# gator.net
KiCad netlist of a schematic drawn in EAGLE
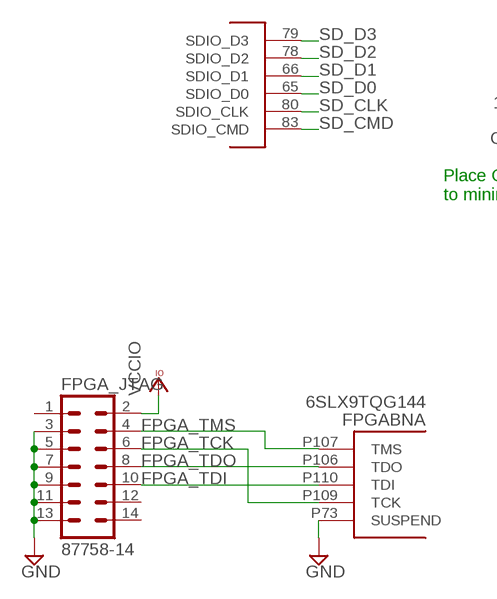
[diagram p0: schematic, sheet 1, part 1 of 2]
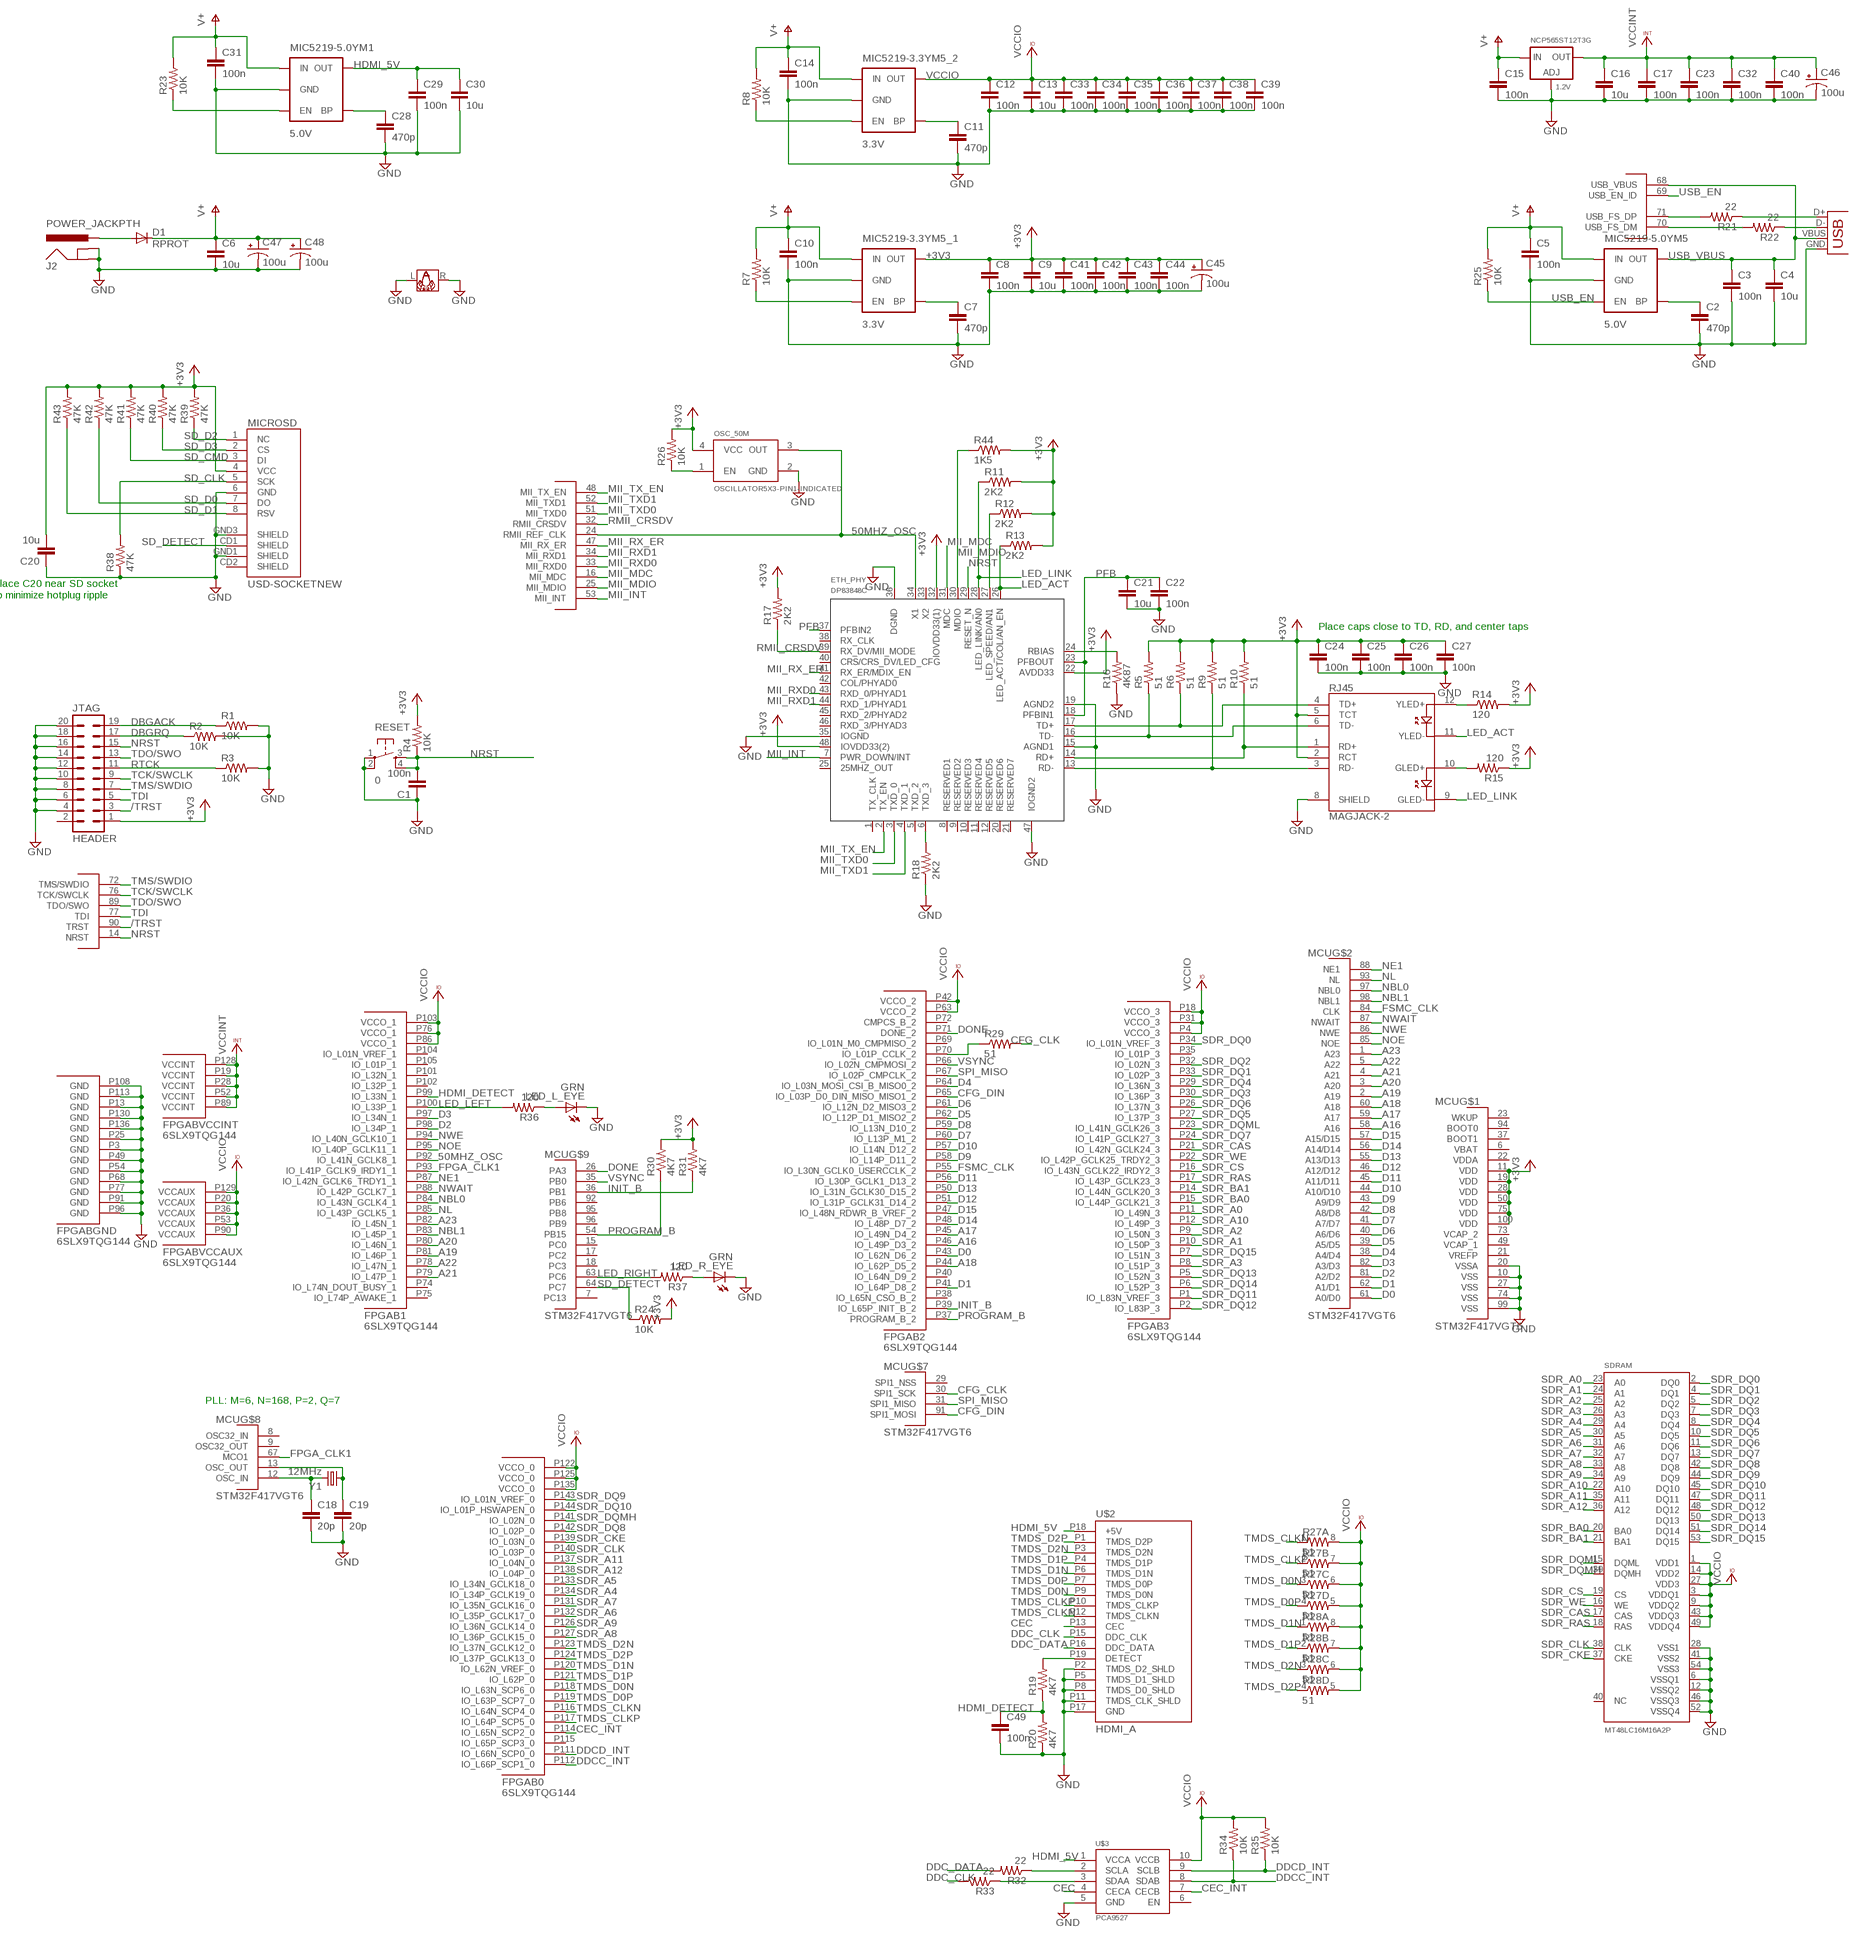
[diagram p1: schematic, sheet 1, part 2 of 2]

(export (version "E")
  (design (tool "Eeschema 10.0.6"))
  (components
    (comp (ref "C1")
      (value "100n")
      (footprint "eagle-import:0603-CAP")
      (libsource (lib "eagle-import") (part "CAP0603-CAP"))
    )
    (comp (ref "C2")
      (value "470p")
      (footprint "eagle-import:0603-CAP")
      (libsource (lib "eagle-import") (part "CAP0603-CAP"))
    )
    (comp (ref "C3")
      (value "100n")
      (footprint "eagle-import:0603-CAP")
      (libsource (lib "eagle-import") (part "CAP0603-CAP"))
    )
    (comp (ref "C4")
      (value "10u")
      (footprint "eagle-import:0603-CAP")
      (libsource (lib "eagle-import") (part "CAP0603-CAP"))
    )
    (comp (ref "C5")
      (value "100n")
      (footprint "eagle-import:0603-CAP")
      (libsource (lib "eagle-import") (part "CAP0603-CAP"))
    )
    (comp (ref "C6")
      (value "10u")
      (footprint "eagle-import:0603-CAP")
      (libsource (lib "eagle-import") (part "CAP0603-CAP"))
    )
    (comp (ref "C7")
      (value "470p")
      (footprint "eagle-import:0603-CAP")
      (libsource (lib "eagle-import") (part "CAP0603-CAP"))
    )
    (comp (ref "C8")
      (value "100n")
      (footprint "eagle-import:0603-CAP")
      (libsource (lib "eagle-import") (part "CAP0603-CAP"))
    )
    (comp (ref "C9")
      (value "10u")
      (footprint "eagle-import:0603-CAP")
      (libsource (lib "eagle-import") (part "CAP0603-CAP"))
    )
    (comp (ref "C10")
      (value "100n")
      (footprint "eagle-import:0603-CAP")
      (libsource (lib "eagle-import") (part "CAP0603-CAP"))
    )
    (comp (ref "C11")
      (value "470p")
      (footprint "eagle-import:0603-CAP")
      (libsource (lib "eagle-import") (part "CAP0603-CAP"))
    )
    (comp (ref "C12")
      (value "100n")
      (footprint "eagle-import:0603-CAP")
      (libsource (lib "eagle-import") (part "CAP0603-CAP"))
    )
    (comp (ref "C13")
      (value "10u")
      (footprint "eagle-import:0603-CAP")
      (libsource (lib "eagle-import") (part "CAP0603-CAP"))
    )
    (comp (ref "C14")
      (value "100n")
      (footprint "eagle-import:0603-CAP")
      (libsource (lib "eagle-import") (part "CAP0603-CAP"))
    )
    (comp (ref "C15")
      (value "100n")
      (footprint "eagle-import:0603-CAP")
      (libsource (lib "eagle-import") (part "CAP0603-CAP"))
    )
    (comp (ref "C16")
      (value "10u")
      (footprint "eagle-import:0603-CAP")
      (libsource (lib "eagle-import") (part "CAP0603-CAP"))
    )
    (comp (ref "C17")
      (value "100n")
      (footprint "eagle-import:0603-CAP")
      (libsource (lib "eagle-import") (part "CAP0603-CAP"))
    )
    (comp (ref "C18")
      (value "20p")
      (footprint "eagle-import:0603-CAP")
      (libsource (lib "eagle-import") (part "CAP0603-CAP"))
    )
    (comp (ref "C19")
      (value "20p")
      (footprint "eagle-import:0603-CAP")
      (libsource (lib "eagle-import") (part "CAP0603-CAP"))
    )
    (comp (ref "C20")
      (value "10u")
      (footprint "eagle-import:0603-CAP")
      (libsource (lib "eagle-import") (part "CAP0603-CAP"))
    )
    (comp (ref "C21")
      (value "10u")
      (footprint "eagle-import:0603-CAP")
      (libsource (lib "eagle-import") (part "CAP0603-CAP"))
    )
    (comp (ref "C22")
      (value "100n")
      (footprint "eagle-import:0603-CAP")
      (libsource (lib "eagle-import") (part "CAP0603-CAP"))
    )
    (comp (ref "C23")
      (value "100n")
      (footprint "eagle-import:0603-CAP")
      (libsource (lib "eagle-import") (part "CAP0603-CAP"))
    )
    (comp (ref "C24")
      (value "100n")
      (footprint "eagle-import:0603-CAP")
      (libsource (lib "eagle-import") (part "CAP0603-CAP"))
    )
    (comp (ref "C25")
      (value "100n")
      (footprint "eagle-import:0603-CAP")
      (libsource (lib "eagle-import") (part "CAP0603-CAP"))
    )
    (comp (ref "C26")
      (value "100n")
      (footprint "eagle-import:0603-CAP")
      (libsource (lib "eagle-import") (part "CAP0603-CAP"))
    )
    (comp (ref "C27")
      (value "100n")
      (footprint "eagle-import:0603-CAP")
      (libsource (lib "eagle-import") (part "CAP0603-CAP"))
    )
    (comp (ref "C28")
      (value "470p")
      (footprint "eagle-import:0603-CAP")
      (libsource (lib "eagle-import") (part "CAP0603-CAP"))
    )
    (comp (ref "C29")
      (value "100n")
      (footprint "eagle-import:0603-CAP")
      (libsource (lib "eagle-import") (part "CAP0603-CAP"))
    )
    (comp (ref "C30")
      (value "10u")
      (footprint "eagle-import:0603-CAP")
      (libsource (lib "eagle-import") (part "CAP0603-CAP"))
    )
    (comp (ref "C31")
      (value "100n")
      (footprint "eagle-import:0603-CAP")
      (libsource (lib "eagle-import") (part "CAP0603-CAP"))
    )
    (comp (ref "C32")
      (value "100n")
      (footprint "eagle-import:0603-CAP")
      (libsource (lib "eagle-import") (part "CAP0603-CAP"))
    )
    (comp (ref "C33")
      (value "100n")
      (footprint "eagle-import:0603-CAP")
      (libsource (lib "eagle-import") (part "CAP0603-CAP"))
    )
    (comp (ref "C34")
      (value "100n")
      (footprint "eagle-import:0603-CAP")
      (libsource (lib "eagle-import") (part "CAP0603-CAP"))
    )
    (comp (ref "C35")
      (value "100n")
      (footprint "eagle-import:0603-CAP")
      (libsource (lib "eagle-import") (part "CAP0603-CAP"))
    )
    (comp (ref "C36")
      (value "100n")
      (footprint "eagle-import:0603-CAP")
      (libsource (lib "eagle-import") (part "CAP0603-CAP"))
    )
    (comp (ref "C37")
      (value "100n")
      (footprint "eagle-import:0603-CAP")
      (libsource (lib "eagle-import") (part "CAP0603-CAP"))
    )
    (comp (ref "C38")
      (value "100n")
      (footprint "eagle-import:0603-CAP")
      (libsource (lib "eagle-import") (part "CAP0603-CAP"))
    )
    (comp (ref "C39")
      (value "100n")
      (footprint "eagle-import:0603-CAP")
      (libsource (lib "eagle-import") (part "CAP0603-CAP"))
    )
    (comp (ref "C40")
      (value "100n")
      (footprint "eagle-import:0603-CAP")
      (libsource (lib "eagle-import") (part "CAP0603-CAP"))
    )
    (comp (ref "C41")
      (value "100n")
      (footprint "eagle-import:0603-CAP")
      (libsource (lib "eagle-import") (part "CAP0603-CAP"))
    )
    (comp (ref "C42")
      (value "100n")
      (footprint "eagle-import:0603-CAP")
      (libsource (lib "eagle-import") (part "CAP0603-CAP"))
    )
    (comp (ref "C43")
      (value "100n")
      (footprint "eagle-import:0603-CAP")
      (libsource (lib "eagle-import") (part "CAP0603-CAP"))
    )
    (comp (ref "C44")
      (value "100n")
      (footprint "eagle-import:0603-CAP")
      (libsource (lib "eagle-import") (part "CAP0603-CAP"))
    )
    (comp (ref "C45")
      (value "100u")
      (footprint "eagle-import:CPOL-RADIAL-100UF-25V")
      (libsource (lib "eagle-import") (part "CAP_POLPTH1"))
    )
    (comp (ref "C46")
      (value "100u")
      (footprint "eagle-import:CPOL-RADIAL-100UF-25V")
      (libsource (lib "eagle-import") (part "CAP_POLPTH1"))
    )
    (comp (ref "C47")
      (value "100u")
      (footprint "eagle-import:CPOL-RADIAL-100UF-25V")
      (libsource (lib "eagle-import") (part "CAP_POLPTH1"))
    )
    (comp (ref "C48")
      (value "100u")
      (footprint "eagle-import:CPOL-RADIAL-100UF-25V")
      (libsource (lib "eagle-import") (part "CAP_POLPTH1"))
    )
    (comp (ref "C49")
      (value "100n")
      (footprint "eagle-import:0603-CAP")
      (libsource (lib "eagle-import") (part "CAP0603-CAP"))
    )
    (comp (ref "D1")
      (value "RPROT")
      (footprint "eagle-import:DIODE-1N4001")
      (fields (field (name "MANF") "STMicroelectronics"))
      (libsource (lib "eagle-import") (part "DIODEPTH"))
    )
    (comp (ref "ETH_PHY")
      (value "DP83848C")
      (footprint "eagle-import:LQFP-48")
      (fields (field (name "MANF") "Texas Instruments"))
      (libsource (lib "eagle-import") (part "DP83848C"))
    )
    (comp (ref "FPGA")
      (value "6SLX9TQG144")
      (footprint "eagle-import:TQ144")
      (fields
        (field (name "DIGIKEY#") "122-1745-ND")
        (field (name "MANF") "Xilinx Inc")
        (field (name "MANF#") "XC6SLX9-2TQG144C")
      )
      (libsource (lib "eagle-import") (part "6SLX9TQG144"))
    )
    (comp (ref "FPGA_JTAG")
      (value "87758-14")
      (footprint "eagle-import:87758-14")
      (fields (field (name "MANF") "Assmann WSW Components"))
      (libsource (lib "eagle-import") (part "87758-14"))
    )
    (comp (ref "J2")
      (value "POWER_JACKPTH")
      (footprint "eagle-import:POWER_JACK_PTH")
      (fields (field (name "MANF") "CUI Inc"))
      (libsource (lib "eagle-import") (part "POWER_JACKPTH"))
    )
    (comp (ref "JTAG")
      (value "HEADER")
      (footprint "eagle-import:ML20")
      (fields (field (name "MANF") "Sullins Connector Solutions"))
      (libsource (lib "eagle-import") (part "ML20"))
    )
    (comp (ref "LED_L_EYE")
      (value "GRN")
      (footprint "eagle-import:LED3MM")
      (fields (field (name "MANF") "Lite-On Inc"))
      (libsource (lib "eagle-import") (part "LED3MM"))
    )
    (comp (ref "LED_R_EYE")
      (value "GRN")
      (footprint "eagle-import:LED3MM")
      (fields (field (name "MANF") "Lite-On Inc"))
      (libsource (lib "eagle-import") (part "LED3MM"))
    )
    (comp (ref "MCU")
      (value "STM32F417VGT6")
      (footprint "eagle-import:LQFP-100")
      (fields
        (field (name "DIGIKEY#") "497-11900-ND")
        (field (name "MANF") "STMicroelectronics")
        (field (name "MANF#") "STM32F417VGT6")
      )
      (libsource (lib "eagle-import") (part "STM32F417VGT6"))
    )
    (comp (ref "MIC5219-3.3YM5_1")
      (value "3.3V")
      (footprint "eagle-import:SOT23-5")
      (fields (field (name "MANF") "Micrel Inc"))
      (libsource (lib "eagle-import") (part "V_REG_LDOSMD"))
    )
    (comp (ref "MIC5219-3.3YM5_2")
      (value "3.3V")
      (footprint "eagle-import:SOT23-5")
      (fields (field (name "MANF") "Micrel Inc"))
      (libsource (lib "eagle-import") (part "V_REG_LDOSMD"))
    )
    (comp (ref "MIC5219-5.0YM1")
      (value "5.0V")
      (footprint "eagle-import:SOT23-5")
      (fields (field (name "MANF") "Micrel Inc"))
      (libsource (lib "eagle-import") (part "V_REG_LDOSMD"))
    )
    (comp (ref "MIC5219-5.0YM5")
      (value "5.0V")
      (footprint "eagle-import:SOT23-5")
      (fields (field (name "MANF") "Micrel Inc"))
      (libsource (lib "eagle-import") (part "V_REG_LDOSMD"))
    )
    (comp (ref "MICROSD")
      (value "USD-SOCKETNEW")
      (footprint "eagle-import:MICRO-SD-SOCKET-PP")
      (fields (field (name "MANF") "Amphenol Commercial Products"))
      (libsource (lib "eagle-import") (part "USD-SOCKETNEW"))
    )
    (comp (ref "NCP565ST12T3G")
      (value "1.2V")
      (footprint "eagle-import:SOT223-R")
      (fields (field (name "MANF") "ON Semiconductor"))
      (libsource (lib "eagle-import") (part "LM1117SOT223-REFLOW"))
    )
    (comp (ref "OSC_50M")
      (value "OSCILLATOR5X3-PIN1-INDICATED")
      (footprint "eagle-import:CRYSTAL-OSC-SMD-5X3")
      (fields (field (name "MANF") "CTS-Frequency Controls"))
      (libsource (lib "eagle-import") (part "OSCILLATOR5X3-PIN1-INDICATED"))
    )
    (comp (ref "R1")
      (value "10K")
      (footprint "eagle-import:0603-RES")
      (libsource (lib "eagle-import") (part "RESISTOR0603-RES"))
    )
    (comp (ref "R2")
      (value "10K")
      (footprint "eagle-import:0603-RES")
      (libsource (lib "eagle-import") (part "RESISTOR0603-RES"))
    )
    (comp (ref "R3")
      (value "10K")
      (footprint "eagle-import:0603-RES")
      (libsource (lib "eagle-import") (part "RESISTOR0603-RES"))
    )
    (comp (ref "R4")
      (value "10K")
      (footprint "eagle-import:0603-RES")
      (libsource (lib "eagle-import") (part "RESISTOR0603-RES"))
    )
    (comp (ref "R5")
      (value "51")
      (footprint "eagle-import:0603-RES")
      (libsource (lib "eagle-import") (part "RESISTOR0603-RES"))
    )
    (comp (ref "R6")
      (value "51")
      (footprint "eagle-import:0603-RES")
      (libsource (lib "eagle-import") (part "RESISTOR0603-RES"))
    )
    (comp (ref "R7")
      (value "10K")
      (footprint "eagle-import:0603-RES")
      (libsource (lib "eagle-import") (part "RESISTOR0603-RES"))
    )
    (comp (ref "R8")
      (value "10K")
      (footprint "eagle-import:0603-RES")
      (libsource (lib "eagle-import") (part "RESISTOR0603-RES"))
    )
    (comp (ref "R9")
      (value "51")
      (footprint "eagle-import:0603-RES")
      (libsource (lib "eagle-import") (part "RESISTOR0603-RES"))
    )
    (comp (ref "R10")
      (value "51")
      (footprint "eagle-import:0603-RES")
      (libsource (lib "eagle-import") (part "RESISTOR0603-RES"))
    )
    (comp (ref "R11")
      (value "2K2")
      (footprint "eagle-import:0603-RES")
      (libsource (lib "eagle-import") (part "RESISTOR0603-RES"))
    )
    (comp (ref "R12")
      (value "2K2")
      (footprint "eagle-import:0603-RES")
      (libsource (lib "eagle-import") (part "RESISTOR0603-RES"))
    )
    (comp (ref "R13")
      (value "2K2")
      (footprint "eagle-import:0603-RES")
      (libsource (lib "eagle-import") (part "RESISTOR0603-RES"))
    )
    (comp (ref "R14")
      (value "120")
      (footprint "eagle-import:0603-RES")
      (libsource (lib "eagle-import") (part "RESISTOR0603-RES"))
    )
    (comp (ref "R15")
      (value "120")
      (footprint "eagle-import:0603-RES")
      (libsource (lib "eagle-import") (part "RESISTOR0603-RES"))
    )
    (comp (ref "R16")
      (value "4K87")
      (footprint "eagle-import:0603-RES")
      (libsource (lib "eagle-import") (part "RESISTOR0603-RES"))
    )
    (comp (ref "R17")
      (value "2K2")
      (footprint "eagle-import:0603-RES")
      (libsource (lib "eagle-import") (part "RESISTOR0603-RES"))
    )
    (comp (ref "R18")
      (value "2K2")
      (footprint "eagle-import:0603-RES")
      (libsource (lib "eagle-import") (part "RESISTOR0603-RES"))
    )
    (comp (ref "R19")
      (value "4K7")
      (footprint "eagle-import:0603-RES")
      (libsource (lib "eagle-import") (part "RESISTOR0603-RES"))
    )
    (comp (ref "R20")
      (value "4K7")
      (footprint "eagle-import:0603-RES")
      (libsource (lib "eagle-import") (part "RESISTOR0603-RES"))
    )
    (comp (ref "R21")
      (value "22")
      (footprint "eagle-import:0603-RES")
      (libsource (lib "eagle-import") (part "RESISTOR0603-RES"))
    )
    (comp (ref "R22")
      (value "22")
      (footprint "eagle-import:0603-RES")
      (libsource (lib "eagle-import") (part "RESISTOR0603-RES"))
    )
    (comp (ref "R23")
      (value "10K")
      (footprint "eagle-import:0603-RES")
      (libsource (lib "eagle-import") (part "RESISTOR0603-RES"))
    )
    (comp (ref "R24")
      (value "10K")
      (footprint "eagle-import:0603-RES")
      (libsource (lib "eagle-import") (part "RESISTOR0603-RES"))
    )
    (comp (ref "R25")
      (value "10K")
      (footprint "eagle-import:0603-RES")
      (libsource (lib "eagle-import") (part "RESISTOR0603-RES"))
    )
    (comp (ref "R26")
      (value "10K")
      (footprint "eagle-import:0603-RES")
      (libsource (lib "eagle-import") (part "RESISTOR0603-RES"))
    )
    (comp (ref "R27")
      (value "51")
      (footprint "eagle-import:0603-ARV")
      (fields
        (field (name "MANF") "Yageo")
        (field (name "DIGIKEY#") "YC164J-51CT-ND")
        (field (name "MANF#") "YC164-JR-0751RL")
      )
      (libsource (lib "eagle-import") (part "RESISTOR-ARRAY0603-ARV"))
    )
    (comp (ref "R28")
      (value "51")
      (footprint "eagle-import:0603-ARV")
      (fields
        (field (name "MANF") "Yageo")
        (field (name "DIGIKEY#") "YC164J-51CT-ND")
        (field (name "MANF#") "YC164-JR-0751RL")
      )
      (libsource (lib "eagle-import") (part "RESISTOR-ARRAY0603-ARV"))
    )
    (comp (ref "R29")
      (value "51")
      (footprint "eagle-import:0603-RES")
      (libsource (lib "eagle-import") (part "RESISTOR0603-RES"))
    )
    (comp (ref "R30")
      (value "4K7")
      (footprint "eagle-import:0603-RES")
      (libsource (lib "eagle-import") (part "RESISTOR0603-RES"))
    )
    (comp (ref "R31")
      (value "4K7")
      (footprint "eagle-import:0603-RES")
      (libsource (lib "eagle-import") (part "RESISTOR0603-RES"))
    )
    (comp (ref "R32")
      (value "22")
      (footprint "eagle-import:0603-RES")
      (libsource (lib "eagle-import") (part "RESISTOR0603-RES"))
    )
    (comp (ref "R33")
      (value "22")
      (footprint "eagle-import:0603-RES")
      (libsource (lib "eagle-import") (part "RESISTOR0603-RES"))
    )
    (comp (ref "R34")
      (value "10K")
      (footprint "eagle-import:0603-RES")
      (libsource (lib "eagle-import") (part "RESISTOR0603-RES"))
    )
    (comp (ref "R35")
      (value "10K")
      (footprint "eagle-import:0603-RES")
      (libsource (lib "eagle-import") (part "RESISTOR0603-RES"))
    )
    (comp (ref "R36")
      (value "120")
      (footprint "eagle-import:0603-RES")
      (libsource (lib "eagle-import") (part "RESISTOR0603-RES"))
    )
    (comp (ref "R37")
      (value "120")
      (footprint "eagle-import:0603-RES")
      (libsource (lib "eagle-import") (part "RESISTOR0603-RES"))
    )
    (comp (ref "R38")
      (value "47K")
      (footprint "eagle-import:0603-RES")
      (libsource (lib "eagle-import") (part "RESISTOR0603-RES"))
    )
    (comp (ref "R39")
      (value "47K")
      (footprint "eagle-import:0603-RES")
      (libsource (lib "eagle-import") (part "RESISTOR0603-RES"))
    )
    (comp (ref "R40")
      (value "47K")
      (footprint "eagle-import:0603-RES")
      (libsource (lib "eagle-import") (part "RESISTOR0603-RES"))
    )
    (comp (ref "R41")
      (value "47K")
      (footprint "eagle-import:0603-RES")
      (libsource (lib "eagle-import") (part "RESISTOR0603-RES"))
    )
    (comp (ref "R42")
      (value "47K")
      (footprint "eagle-import:0603-RES")
      (libsource (lib "eagle-import") (part "RESISTOR0603-RES"))
    )
    (comp (ref "R43")
      (value "47K")
      (footprint "eagle-import:0603-RES")
      (libsource (lib "eagle-import") (part "RESISTOR0603-RES"))
    )
    (comp (ref "R44")
      (value "1K5")
      (footprint "eagle-import:0603-RES")
      (libsource (lib "eagle-import") (part "RESISTOR0603-RES"))
    )
    (comp (ref "RESET")
      (value "0")
      (footprint "eagle-import:TACTILE-PTH")
      (libsource (lib "eagle-import") (part "TAC_SWITCHPTH"))
    )
    (comp (ref "RJ45")
      (value "MAGJACK-2")
      (footprint "eagle-import:MAGJACK-19938")
      (fields (field (name "MANF") "Stewart Connector"))
      (libsource (lib "eagle-import") (part "MAGJACK-2"))
    )
    (comp (ref "SDRAM")
      (value "MT48LC16M16A2P")
      (footprint "eagle-import:TSOP54-400")
      (fields (field (name "MANF") "Micron Technology Inc"))
      (libsource (lib "eagle-import") (part "MT48LC16M16A2P"))
    )
    (comp (ref "U$2")
      (value "HDMI_A")
      (footprint "eagle-import:HDMI_A_SMT")
      (fields (field (name "MANF") "Molex Inc"))
      (libsource (lib "eagle-import") (part "HDMI_A"))
    )
    (comp (ref "U$3")
      (value "PCA9527")
      (footprint "eagle-import:TSSOP10")
      (fields (field (name "MANF") "NXP Semiconductors"))
      (libsource (lib "eagle-import") (part "PCA9527"))
    )
    (comp (ref "U$4")
      (value "GATOR_HEAD")
      (footprint "eagle-import:GATOR_HEAD")
      (fields (field (name "MANF") "CUI Inc"))
      (libsource (lib "eagle-import") (part "GATOR_HEAD"))
    )
    (comp (ref "X1")
      (value "USB-A-S")
      (footprint "eagle-import:USB-A-S")
      (fields (field (name "MANF") "CNC Tech"))
      (libsource (lib "eagle-import") (part "USB-A-S"))
    )
    (comp (ref "Y1")
      (value "12MHz")
      (footprint "eagle-import:HC49US")
      (fields (field (name "MANF") "CTS-Frequency Controls"))
      (libsource (lib "eagle-import") (part "CRYSTALHC49US"))
    )
  )
  (nets
    (net (code "1") (name "+3V3") (class "Default")
      (node (ref "C20") (pin "2") (pinfunction "2_2") (pintype "passive"))
      (node (ref "C24") (pin "1") (pinfunction "1_1") (pintype "passive"))
      (node (ref "C25") (pin "1") (pinfunction "1_1") (pintype "passive"))
      (node (ref "C26") (pin "1") (pinfunction "1_1") (pintype "passive"))
      (node (ref "C27") (pin "1") (pinfunction "1_1") (pintype "passive"))
      (node (ref "C41") (pin "1") (pinfunction "1_1") (pintype "passive"))
      (node (ref "C42") (pin "1") (pinfunction "1_1") (pintype "passive"))
      (node (ref "C43") (pin "1") (pinfunction "1_1") (pintype "passive"))
      (node (ref "C44") (pin "1") (pinfunction "1_1") (pintype "passive"))
      (node (ref "C45") (pin "1") (pinfunction "+_1") (pintype "passive"))
      (node (ref "C8") (pin "1") (pinfunction "1_1") (pintype "passive"))
      (node (ref "C9") (pin "1") (pinfunction "1_1") (pintype "passive"))
      (node (ref "ETH_PHY") (pin "22") (pinfunction "AVDD33_22") (pintype "bidirectional"))
      (node (ref "ETH_PHY") (pin "32") (pinfunction "IOVDD33(1)_32") (pintype "bidirectional"))
      (node (ref "ETH_PHY") (pin "48") (pinfunction "IOVDD33(2)_48") (pintype "bidirectional"))
      (node (ref "JTAG") (pin "1") (pinfunction "1_1") (pintype "passive"))
      (node (ref "MCU") (pin "100") (pinfunction "VDD_100") (pintype "bidirectional"))
      (node (ref "MCU") (pin "11") (pinfunction "VDD_11") (pintype "bidirectional"))
      (node (ref "MCU") (pin "19") (pinfunction "VDD_19") (pintype "bidirectional"))
      (node (ref "MCU") (pin "28") (pinfunction "VDD_28") (pintype "bidirectional"))
      (node (ref "MCU") (pin "50") (pinfunction "VDD_50") (pintype "bidirectional"))
      (node (ref "MCU") (pin "75") (pinfunction "VDD_75") (pintype "bidirectional"))
      (node (ref "MIC5219-3.3YM5_1") (pin "5") (pinfunction "OUT_5") (pintype "passive"))
      (node (ref "MICROSD") (pin "4") (pinfunction "VCC_4") (pintype "bidirectional"))
      (node (ref "OSC_50M") (pin "4") (pinfunction "VCC_4") (pintype "bidirectional"))
      (node (ref "R10") (pin "2") (pinfunction "2_2") (pintype "passive"))
      (node (ref "R11") (pin "2") (pinfunction "2_2") (pintype "passive"))
      (node (ref "R12") (pin "2") (pinfunction "2_2") (pintype "passive"))
      (node (ref "R13") (pin "2") (pinfunction "2_2") (pintype "passive"))
      (node (ref "R14") (pin "2") (pinfunction "2_2") (pintype "passive"))
      (node (ref "R15") (pin "1") (pinfunction "1_1") (pintype "passive"))
      (node (ref "R17") (pin "2") (pinfunction "2_2") (pintype "passive"))
      (node (ref "R24") (pin "2") (pinfunction "2_2") (pintype "passive"))
      (node (ref "R26") (pin "2") (pinfunction "2_2") (pintype "passive"))
      (node (ref "R30") (pin "2") (pinfunction "2_2") (pintype "passive"))
      (node (ref "R31") (pin "2") (pinfunction "2_2") (pintype "passive"))
      (node (ref "R39") (pin "2") (pinfunction "2_2") (pintype "passive"))
      (node (ref "R4") (pin "2") (pinfunction "2_2") (pintype "passive"))
      (node (ref "R40") (pin "2") (pinfunction "2_2") (pintype "passive"))
      (node (ref "R41") (pin "2") (pinfunction "2_2") (pintype "passive"))
      (node (ref "R42") (pin "2") (pinfunction "2_2") (pintype "passive"))
      (node (ref "R43") (pin "2") (pinfunction "2_2") (pintype "passive"))
      (node (ref "R44") (pin "2") (pinfunction "2_2") (pintype "passive"))
      (node (ref "R5") (pin "2") (pinfunction "2_2") (pintype "passive"))
      (node (ref "R6") (pin "2") (pinfunction "2_2") (pintype "passive"))
      (node (ref "R9") (pin "2") (pinfunction "2_2") (pintype "passive"))
      (node (ref "RJ45") (pin "2") (pinfunction "RCT_2") (pintype "bidirectional"))
      (node (ref "RJ45") (pin "5") (pinfunction "TCT_5") (pintype "bidirectional"))
    )
    (net (code "2") (name "/50MHZ_OSC") (class "Default")
      (node (ref "ETH_PHY") (pin "34") (pinfunction "X1_34") (pintype "bidirectional"))
      (node (ref "FPGA") (pin "P92") (pinfunction "IO_L41N_GCLK8_1_P92") (pintype "bidirectional"))
      (node (ref "MCU") (pin "24") (pinfunction "RMII_REF_CLK_24") (pintype "bidirectional"))
      (node (ref "OSC_50M") (pin "3") (pinfunction "OUT_3") (pintype "bidirectional"))
    )
    (net (code "3") (name "/A16") (class "Default")
      (node (ref "FPGA") (pin "P46") (pinfunction "IO_L49P_D3_2_P46") (pintype "bidirectional"))
      (node (ref "MCU") (pin "58") (pinfunction "A16_58") (pintype "bidirectional"))
    )
    (net (code "4") (name "/A17") (class "Default")
      (node (ref "FPGA") (pin "P45") (pinfunction "IO_L49N_D4_2_P45") (pintype "bidirectional"))
      (node (ref "MCU") (pin "59") (pinfunction "A17_59") (pintype "bidirectional"))
    )
    (net (code "5") (name "/A18") (class "Default")
      (node (ref "FPGA") (pin "P44") (pinfunction "IO_L62P_D5_2_P44") (pintype "bidirectional"))
      (node (ref "MCU") (pin "60") (pinfunction "A18_60") (pintype "bidirectional"))
    )
    (net (code "6") (name "/A19") (class "Default")
      (node (ref "FPGA") (pin "P81") (pinfunction "IO_L46P_1_P81") (pintype "bidirectional"))
      (node (ref "MCU") (pin "2") (pinfunction "A19_2") (pintype "bidirectional"))
    )
    (net (code "7") (name "/A20") (class "Default")
      (node (ref "FPGA") (pin "P80") (pinfunction "IO_L46N_1_P80") (pintype "bidirectional"))
      (node (ref "MCU") (pin "3") (pinfunction "A20_3") (pintype "bidirectional"))
    )
    (net (code "8") (name "/A21") (class "Default")
      (node (ref "FPGA") (pin "P79") (pinfunction "IO_L47P_1_P79") (pintype "bidirectional"))
      (node (ref "MCU") (pin "4") (pinfunction "A21_4") (pintype "bidirectional"))
    )
    (net (code "9") (name "/A22") (class "Default")
      (node (ref "FPGA") (pin "P78") (pinfunction "IO_L47N_1_P78") (pintype "bidirectional"))
      (node (ref "MCU") (pin "5") (pinfunction "A22_5") (pintype "bidirectional"))
    )
    (net (code "10") (name "/A23") (class "Default")
      (node (ref "FPGA") (pin "P82") (pinfunction "IO_L45N_1_P82") (pintype "bidirectional"))
      (node (ref "MCU") (pin "1") (pinfunction "A23_1") (pintype "bidirectional"))
    )
    (net (code "11") (name "/CEC") (class "Default")
      (node (ref "U$2") (pin "P13") (pinfunction "CEC_P13") (pintype "bidirectional"))
      (node (ref "U$3") (pin "4") (pinfunction "CECA_4") (pintype "bidirectional"))
    )
    (net (code "12") (name "/CEC_INT") (class "Default")
      (node (ref "FPGA") (pin "P114") (pinfunction "IO_L65N_SCP2_0_P114") (pintype "bidirectional"))
      (node (ref "U$3") (pin "7") (pinfunction "CECB_7") (pintype "bidirectional"))
    )
    (net (code "13") (name "/CFG_CLK") (class "Default")
      (node (ref "MCU") (pin "30") (pinfunction "SPI1_SCK_30") (pintype "bidirectional"))
      (node (ref "R29") (pin "2") (pinfunction "2_2") (pintype "passive"))
    )
    (net (code "14") (name "/CFG_DIN") (class "Default")
      (node (ref "FPGA") (pin "P65") (pinfunction "IO_L03P_D0_DIN_MISO_MISO1_2_P65") (pintype "bidirectional"))
      (node (ref "MCU") (pin "91") (pinfunction "SPI1_MOSI_91") (pintype "bidirectional"))
    )
    (net (code "15") (name "/D0") (class "Default")
      (node (ref "FPGA") (pin "P43") (pinfunction "IO_L62N_D6_2_P43") (pintype "bidirectional"))
      (node (ref "MCU") (pin "61") (pinfunction "A0/D0_61") (pintype "bidirectional"))
    )
    (net (code "16") (name "/D1") (class "Default")
      (node (ref "FPGA") (pin "P41") (pinfunction "IO_L64P_D8_2_P41") (pintype "bidirectional"))
      (node (ref "MCU") (pin "62") (pinfunction "A1/D1_62") (pintype "bidirectional"))
    )
    (net (code "17") (name "/D2") (class "Default")
      (node (ref "FPGA") (pin "P98") (pinfunction "IO_L34P_1_P98") (pintype "bidirectional"))
      (node (ref "MCU") (pin "81") (pinfunction "A2/D2_81") (pintype "bidirectional"))
    )
    (net (code "18") (name "/D3") (class "Default")
      (node (ref "FPGA") (pin "P97") (pinfunction "IO_L34N_1_P97") (pintype "bidirectional"))
      (node (ref "MCU") (pin "82") (pinfunction "A3/D3_82") (pintype "bidirectional"))
    )
    (net (code "19") (name "/D4") (class "Default")
      (node (ref "FPGA") (pin "P64") (pinfunction "IO_L03N_MOSI_CSI_B_MISO0_2_P64") (pintype "bidirectional"))
      (node (ref "MCU") (pin "38") (pinfunction "A4/D4_38") (pintype "bidirectional"))
    )
    (net (code "20") (name "/D5") (class "Default")
      (node (ref "FPGA") (pin "P62") (pinfunction "IO_L12P_D1_MISO2_2_P62") (pintype "bidirectional"))
      (node (ref "MCU") (pin "39") (pinfunction "A5/D5_39") (pintype "bidirectional"))
    )
    (net (code "21") (name "/D6") (class "Default")
      (node (ref "FPGA") (pin "P61") (pinfunction "IO_L12N_D2_MISO3_2_P61") (pintype "bidirectional"))
      (node (ref "MCU") (pin "40") (pinfunction "A6/D6_40") (pintype "bidirectional"))
    )
    (net (code "22") (name "/D7") (class "Default")
      (node (ref "FPGA") (pin "P60") (pinfunction "IO_L13P_M1_2_P60") (pintype "bidirectional"))
      (node (ref "MCU") (pin "41") (pinfunction "A7/D7_41") (pintype "bidirectional"))
    )
    (net (code "23") (name "/D8") (class "Default")
      (node (ref "FPGA") (pin "P59") (pinfunction "IO_L13N_D10_2_P59") (pintype "bidirectional"))
      (node (ref "MCU") (pin "42") (pinfunction "A8/D8_42") (pintype "bidirectional"))
    )
    (net (code "24") (name "/D9") (class "Default")
      (node (ref "FPGA") (pin "P58") (pinfunction "IO_L14P_D11_2_P58") (pintype "bidirectional"))
      (node (ref "MCU") (pin "43") (pinfunction "A9/D9_43") (pintype "bidirectional"))
    )
    (net (code "25") (name "/D10") (class "Default")
      (node (ref "FPGA") (pin "P57") (pinfunction "IO_L14N_D12_2_P57") (pintype "bidirectional"))
      (node (ref "MCU") (pin "44") (pinfunction "A10/D10_44") (pintype "bidirectional"))
    )
    (net (code "26") (name "/D11") (class "Default")
      (node (ref "FPGA") (pin "P56") (pinfunction "IO_L30P_GCLK1_D13_2_P56") (pintype "bidirectional"))
      (node (ref "MCU") (pin "45") (pinfunction "A11/D11_45") (pintype "bidirectional"))
    )
    (net (code "27") (name "/D12") (class "Default")
      (node (ref "FPGA") (pin "P51") (pinfunction "IO_L31P_GCLK31_D14_2_P51") (pintype "bidirectional"))
      (node (ref "MCU") (pin "46") (pinfunction "A12/D12_46") (pintype "bidirectional"))
    )
    (net (code "28") (name "/D13") (class "Default")
      (node (ref "FPGA") (pin "P50") (pinfunction "IO_L31N_GCLK30_D15_2_P50") (pintype "bidirectional"))
      (node (ref "MCU") (pin "55") (pinfunction "A13/D13_55") (pintype "bidirectional"))
    )
    (net (code "29") (name "/D14") (class "Default")
      (node (ref "FPGA") (pin "P48") (pinfunction "IO_L48P_D7_2_P48") (pintype "bidirectional"))
      (node (ref "MCU") (pin "56") (pinfunction "A14/D14_56") (pintype "bidirectional"))
    )
    (net (code "30") (name "/D15") (class "Default")
      (node (ref "FPGA") (pin "P47") (pinfunction "IO_L48N_RDWR_B_VREF_2_P47") (pintype "bidirectional"))
      (node (ref "MCU") (pin "57") (pinfunction "A15/D15_57") (pintype "bidirectional"))
    )
    (net (code "31") (name "/DBGACK") (class "Default")
      (node (ref "JTAG") (pin "19") (pinfunction "19_19") (pintype "passive"))
      (node (ref "R1") (pin "1") (pinfunction "1_1") (pintype "passive"))
    )
    (net (code "32") (name "/DBGRQ") (class "Default")
      (node (ref "JTAG") (pin "17") (pinfunction "17_17") (pintype "passive"))
      (node (ref "R2") (pin "1") (pinfunction "1_1") (pintype "passive"))
    )
    (net (code "33") (name "/DDCC_INT") (class "Default")
      (node (ref "FPGA") (pin "P112") (pinfunction "IO_L66P_SCP1_0_P112") (pintype "bidirectional"))
      (node (ref "R34") (pin "1") (pinfunction "1_1") (pintype "passive"))
      (node (ref "U$3") (pin "8") (pinfunction "SDAB_8") (pintype "bidirectional"))
    )
    (net (code "34") (name "/DDCD_INT") (class "Default")
      (node (ref "FPGA") (pin "P111") (pinfunction "IO_L66N_SCP0_0_P111") (pintype "bidirectional"))
      (node (ref "R35") (pin "1") (pinfunction "1_1") (pintype "passive"))
      (node (ref "U$3") (pin "9") (pinfunction "SCLB_9") (pintype "bidirectional"))
    )
    (net (code "35") (name "/DDC_CLK") (class "Default")
      (node (ref "R33") (pin "2") (pinfunction "2_2") (pintype "passive"))
      (node (ref "U$2") (pin "P15") (pinfunction "DDC_CLK_P15") (pintype "bidirectional"))
    )
    (net (code "36") (name "/DDC_DATA") (class "Default")
      (node (ref "R32") (pin "2") (pinfunction "2_2") (pintype "passive"))
      (node (ref "U$2") (pin "P16") (pinfunction "DDC_DATA_P16") (pintype "bidirectional"))
    )
    (net (code "37") (name "/DONE") (class "Default")
      (node (ref "FPGA") (pin "P71") (pinfunction "DONE_2_P71") (pintype "bidirectional"))
      (node (ref "MCU") (pin "26") (pinfunction "PA3_26") (pintype "bidirectional"))
    )
    (net (code "38") (name "/FPGA_CLK1") (class "Default")
      (node (ref "FPGA") (pin "P93") (pinfunction "IO_L41P_GCLK9_IRDY1_1_P93") (pintype "bidirectional"))
      (node (ref "MCU") (pin "67") (pinfunction "MCO1_67") (pintype "bidirectional"))
    )
    (net (code "39") (name "/FPGA_TCK") (class "Default")
      (node (ref "FPGA") (pin "P109") (pinfunction "TCK_P109") (pintype "input"))
      (node (ref "FPGA_JTAG") (pin "6") (pinfunction "6_6") (pintype "passive"))
    )
    (net (code "40") (name "/FPGA_TDI") (class "Default")
      (node (ref "FPGA") (pin "P110") (pinfunction "TDI_P110") (pintype "input"))
      (node (ref "FPGA_JTAG") (pin "10") (pinfunction "10_10") (pintype "passive"))
    )
    (net (code "41") (name "/FPGA_TDO") (class "Default")
      (node (ref "FPGA") (pin "P106") (pinfunction "TDO_P106") (pintype "output"))
      (node (ref "FPGA_JTAG") (pin "8") (pinfunction "8_8") (pintype "passive"))
    )
    (net (code "42") (name "/FPGA_TMS") (class "Default")
      (node (ref "FPGA") (pin "P107") (pinfunction "TMS_P107") (pintype "input"))
      (node (ref "FPGA_JTAG") (pin "4") (pinfunction "4_4") (pintype "passive"))
    )
    (net (code "43") (name "/FSMC_CLK") (class "Default")
      (node (ref "FPGA") (pin "P55") (pinfunction "IO_L30N_GCLK0_USERCCLK_2_P55") (pintype "bidirectional"))
      (node (ref "MCU") (pin "84") (pinfunction "CLK_84") (pintype "bidirectional"))
    )
    (net (code "44") (name "/HDMI_5V") (class "Default")
      (node (ref "C29") (pin "1") (pinfunction "1_1") (pintype "passive"))
      (node (ref "C30") (pin "1") (pinfunction "1_1") (pintype "passive"))
      (node (ref "MIC5219-5.0YM1") (pin "5") (pinfunction "OUT_5") (pintype "passive"))
      (node (ref "U$2") (pin "P18") (pinfunction "+5V_P18") (pintype "bidirectional"))
      (node (ref "U$3") (pin "1") (pinfunction "VCCA_1") (pintype "bidirectional"))
    )
    (net (code "45") (name "/HDMI_DETECT") (class "Default")
      (node (ref "C49") (pin "1") (pinfunction "1_1") (pintype "passive"))
      (node (ref "FPGA") (pin "P99") (pinfunction "IO_L33N_1_P99") (pintype "bidirectional"))
      (node (ref "R19") (pin "1") (pinfunction "1_1") (pintype "passive"))
      (node (ref "R20") (pin "2") (pinfunction "2_2") (pintype "passive"))
    )
    (net (code "46") (name "/INIT_B") (class "Default")
      (node (ref "FPGA") (pin "P39") (pinfunction "IO_L65P_INIT_B_2_P39") (pintype "bidirectional"))
      (node (ref "MCU") (pin "36") (pinfunction "PB1_36") (pintype "bidirectional"))
      (node (ref "R31") (pin "1") (pinfunction "1_1") (pintype "passive"))
    )
    (net (code "47") (name "/LED_ACT") (class "Default")
      (node (ref "ETH_PHY") (pin "26") (pinfunction "LED_ACT/COL/AN_EN_26") (pintype "bidirectional"))
      (node (ref "R13") (pin "1") (pinfunction "1_1") (pintype "passive"))
      (node (ref "RJ45") (pin "11") (pinfunction "YLED-_11") (pintype "bidirectional"))
    )
    (net (code "48") (name "/LED_LEFT") (class "Default")
      (node (ref "FPGA") (pin "P100") (pinfunction "IO_L33P_1_P100") (pintype "bidirectional"))
      (node (ref "R36") (pin "2") (pinfunction "2_2") (pintype "passive"))
    )
    (net (code "49") (name "/LED_LINK") (class "Default")
      (node (ref "ETH_PHY") (pin "28") (pinfunction "LED_LINK/AN0_28") (pintype "bidirectional"))
      (node (ref "R11") (pin "1") (pinfunction "1_1") (pintype "passive"))
      (node (ref "RJ45") (pin "9") (pinfunction "GLED-_9") (pintype "bidirectional"))
    )
    (net (code "50") (name "/LED_RIGHT") (class "Default")
      (node (ref "MCU") (pin "63") (pinfunction "PC6_63") (pintype "bidirectional"))
      (node (ref "R37") (pin "2") (pinfunction "2_2") (pintype "passive"))
    )
    (net (code "51") (name "/MII_INT") (class "Default")
      (node (ref "ETH_PHY") (pin "7") (pinfunction "PWR_DOWN/INT_7") (pintype "bidirectional"))
      (node (ref "MCU") (pin "53") (pinfunction "MII_INT_53") (pintype "bidirectional"))
    )
    (net (code "52") (name "/MII_MDC") (class "Default")
      (node (ref "ETH_PHY") (pin "31") (pinfunction "MDC_31") (pintype "bidirectional"))
      (node (ref "MCU") (pin "16") (pinfunction "MII_MDC_16") (pintype "bidirectional"))
    )
    (net (code "53") (name "/MII_MDIO") (class "Default")
      (node (ref "ETH_PHY") (pin "30") (pinfunction "MDIO_30") (pintype "bidirectional"))
      (node (ref "MCU") (pin "25") (pinfunction "MII_MDIO_25") (pintype "bidirectional"))
      (node (ref "R44") (pin "1") (pinfunction "1_1") (pintype "passive"))
    )
    (net (code "54") (name "/MII_RXD0") (class "Default")
      (node (ref "ETH_PHY") (pin "43") (pinfunction "RXD_0/PHYAD1_43") (pintype "bidirectional"))
      (node (ref "MCU") (pin "33") (pinfunction "MII_RXD0_33") (pintype "bidirectional"))
    )
    (net (code "55") (name "/MII_RXD1") (class "Default")
      (node (ref "ETH_PHY") (pin "44") (pinfunction "RXD_1/PHYAD1_44") (pintype "bidirectional"))
      (node (ref "MCU") (pin "34") (pinfunction "MII_RXD1_34") (pintype "bidirectional"))
    )
    (net (code "56") (name "/MII_RX_ER") (class "Default")
      (node (ref "ETH_PHY") (pin "41") (pinfunction "RX_ER/MDIX_EN_41") (pintype "bidirectional"))
      (node (ref "MCU") (pin "47") (pinfunction "MII_RX_ER_47") (pintype "bidirectional"))
    )
    (net (code "57") (name "/MII_TXD0") (class "Default")
      (node (ref "ETH_PHY") (pin "3") (pinfunction "TXD_0_3") (pintype "bidirectional"))
      (node (ref "MCU") (pin "51") (pinfunction "MII_TXD0_51") (pintype "bidirectional"))
    )
    (net (code "58") (name "/MII_TXD1") (class "Default")
      (node (ref "ETH_PHY") (pin "4") (pinfunction "TXD_1_4") (pintype "bidirectional"))
      (node (ref "MCU") (pin "52") (pinfunction "MII_TXD1_52") (pintype "bidirectional"))
    )
    (net (code "59") (name "/MII_TX_EN") (class "Default")
      (node (ref "ETH_PHY") (pin "2") (pinfunction "TX_EN_2") (pintype "bidirectional"))
      (node (ref "MCU") (pin "48") (pinfunction "MII_TX_EN_48") (pintype "bidirectional"))
    )
    (net (code "60") (name "/NBL0") (class "Default")
      (node (ref "FPGA") (pin "P84") (pinfunction "IO_L43N_GCLK4_1_P84") (pintype "bidirectional"))
      (node (ref "MCU") (pin "97") (pinfunction "NBL0_97") (pintype "bidirectional"))
    )
    (net (code "61") (name "/NBL1") (class "Default")
      (node (ref "FPGA") (pin "P83") (pinfunction "IO_L45P_1_P83") (pintype "bidirectional"))
      (node (ref "MCU") (pin "98") (pinfunction "NBL1_98") (pintype "bidirectional"))
    )
    (net (code "62") (name "/NE1") (class "Default")
      (node (ref "FPGA") (pin "P87") (pinfunction "IO_L42N_GCLK6_TRDY1_1_P87") (pintype "bidirectional"))
      (node (ref "MCU") (pin "88") (pinfunction "NE1_88") (pintype "bidirectional"))
    )
    (net (code "63") (name "/NL") (class "Default")
      (node (ref "FPGA") (pin "P85") (pinfunction "IO_L43P_GCLK5_1_P85") (pintype "bidirectional"))
      (node (ref "MCU") (pin "93") (pinfunction "NL_93") (pintype "bidirectional"))
    )
    (net (code "64") (name "/NOE") (class "Default")
      (node (ref "FPGA") (pin "P95") (pinfunction "IO_L40P_GCLK11_1_P95") (pintype "bidirectional"))
      (node (ref "MCU") (pin "85") (pinfunction "NOE_85") (pintype "bidirectional"))
    )
    (net (code "65") (name "/NRST") (class "Default")
      (node (ref "C1") (pin "2") (pinfunction "2_2") (pintype "passive"))
      (node (ref "ETH_PHY") (pin "29") (pinfunction "RESET_N_29") (pintype "bidirectional"))
      (node (ref "JTAG") (pin "15") (pinfunction "15_15") (pintype "passive"))
      (node (ref "MCU") (pin "14") (pinfunction "NRST_14") (pintype "bidirectional"))
      (node (ref "R4") (pin "1") (pinfunction "1_1") (pintype "passive"))
      (node (ref "RESET") (pin "3") (pinfunction "3_3") (pintype "passive"))
      (node (ref "RESET") (pin "4") (pinfunction "4_4") (pintype "passive"))
    )
    (net (code "66") (name "/NWAIT") (class "Default")
      (node (ref "FPGA") (pin "P88") (pinfunction "IO_L42P_GCLK7_1_P88") (pintype "bidirectional"))
      (node (ref "MCU") (pin "87") (pinfunction "NWAIT_87") (pintype "bidirectional"))
    )
    (net (code "67") (name "/NWE") (class "Default")
      (node (ref "FPGA") (pin "P94") (pinfunction "IO_L40N_GCLK10_1_P94") (pintype "bidirectional"))
      (node (ref "MCU") (pin "86") (pinfunction "NWE_86") (pintype "bidirectional"))
    )
    (net (code "68") (name "/PFB") (class "Default")
      (node (ref "C21") (pin "1") (pinfunction "1_1") (pintype "passive"))
      (node (ref "C22") (pin "1") (pinfunction "1_1") (pintype "passive"))
      (node (ref "ETH_PHY") (pin "18") (pinfunction "PFBIN1_18") (pintype "bidirectional"))
      (node (ref "ETH_PHY") (pin "23") (pinfunction "PFBOUT_23") (pintype "bidirectional"))
      (node (ref "ETH_PHY") (pin "37") (pinfunction "PFBIN2_37") (pintype "bidirectional"))
    )
    (net (code "69") (name "/PROGRAM_B") (class "Default")
      (node (ref "FPGA") (pin "P37") (pinfunction "PROGRAM_B_2_P37") (pintype "input"))
      (node (ref "MCU") (pin "54") (pinfunction "PB15_54") (pintype "bidirectional"))
      (node (ref "R30") (pin "1") (pinfunction "1_1") (pintype "passive"))
    )
    (net (code "70") (name "/RMII_CRSDV") (class "Default")
      (node (ref "ETH_PHY") (pin "39") (pinfunction "RX_DV/MII_MODE_39") (pintype "bidirectional"))
      (node (ref "MCU") (pin "32") (pinfunction "RMII_CRSDV_32") (pintype "bidirectional"))
      (node (ref "R17") (pin "1") (pinfunction "1_1") (pintype "passive"))
    )
    (net (code "71") (name "/RTCK") (class "Default")
      (node (ref "JTAG") (pin "11") (pinfunction "11_11") (pintype "passive"))
      (node (ref "R3") (pin "1") (pinfunction "1_1") (pintype "passive"))
    )
    (net (code "72") (name "/SDR_A0") (class "Default")
      (node (ref "FPGA") (pin "P11") (pinfunction "IO_L49N_3_P11") (pintype "bidirectional"))
      (node (ref "SDRAM") (pin "23") (pinfunction "A0_23") (pintype "bidirectional"))
    )
    (net (code "73") (name "/SDR_A1") (class "Default")
      (node (ref "FPGA") (pin "P10") (pinfunction "IO_L50P_3_P10") (pintype "bidirectional"))
      (node (ref "SDRAM") (pin "24") (pinfunction "A1_24") (pintype "bidirectional"))
    )
    (net (code "74") (name "/SDR_A2") (class "Default")
      (node (ref "FPGA") (pin "P9") (pinfunction "IO_L50N_3_P9") (pintype "bidirectional"))
      (node (ref "SDRAM") (pin "25") (pinfunction "A2_25") (pintype "bidirectional"))
    )
    (net (code "75") (name "/SDR_A3") (class "Default")
      (node (ref "FPGA") (pin "P8") (pinfunction "IO_L51P_3_P8") (pintype "bidirectional"))
      (node (ref "SDRAM") (pin "26") (pinfunction "A3_26") (pintype "bidirectional"))
    )
    (net (code "76") (name "/SDR_A4") (class "Default")
      (node (ref "FPGA") (pin "P134") (pinfunction "IO_L34P_GCLK19_0_P134") (pintype "bidirectional"))
      (node (ref "SDRAM") (pin "29") (pinfunction "A4_29") (pintype "bidirectional"))
    )
    (net (code "77") (name "/SDR_A5") (class "Default")
      (node (ref "FPGA") (pin "P133") (pinfunction "IO_L34N_GCLK18_0_P133") (pintype "bidirectional"))
      (node (ref "SDRAM") (pin "30") (pinfunction "A5_30") (pintype "bidirectional"))
    )
    (net (code "78") (name "/SDR_A6") (class "Default")
      (node (ref "FPGA") (pin "P132") (pinfunction "IO_L35P_GCLK17_0_P132") (pintype "bidirectional"))
      (node (ref "SDRAM") (pin "31") (pinfunction "A6_31") (pintype "bidirectional"))
    )
    (net (code "79") (name "/SDR_A7") (class "Default")
      (node (ref "FPGA") (pin "P131") (pinfunction "IO_L35N_GCLK16_0_P131") (pintype "bidirectional"))
      (node (ref "SDRAM") (pin "32") (pinfunction "A7_32") (pintype "bidirectional"))
    )
    (net (code "80") (name "/SDR_A8") (class "Default")
      (node (ref "FPGA") (pin "P127") (pinfunction "IO_L36P_GCLK15_0_P127") (pintype "bidirectional"))
      (node (ref "SDRAM") (pin "33") (pinfunction "A8_33") (pintype "bidirectional"))
    )
    (net (code "81") (name "/SDR_A9") (class "Default")
      (node (ref "FPGA") (pin "P126") (pinfunction "IO_L36N_GCLK14_0_P126") (pintype "bidirectional"))
      (node (ref "SDRAM") (pin "34") (pinfunction "A9_34") (pintype "bidirectional"))
    )
    (net (code "82") (name "/SDR_A10") (class "Default")
      (node (ref "FPGA") (pin "P12") (pinfunction "IO_L49P_3_P12") (pintype "bidirectional"))
      (node (ref "SDRAM") (pin "22") (pinfunction "A10_22") (pintype "bidirectional"))
    )
    (net (code "83") (name "/SDR_A11") (class "Default")
      (node (ref "FPGA") (pin "P137") (pinfunction "IO_L04N_0_P137") (pintype "bidirectional"))
      (node (ref "SDRAM") (pin "35") (pinfunction "A11_35") (pintype "bidirectional"))
    )
    (net (code "84") (name "/SDR_A12") (class "Default")
      (node (ref "FPGA") (pin "P138") (pinfunction "IO_L04P_0_P138") (pintype "bidirectional"))
      (node (ref "SDRAM") (pin "36") (pinfunction "A12_36") (pintype "bidirectional"))
    )
    (net (code "85") (name "/SDR_BA0") (class "Default")
      (node (ref "FPGA") (pin "P15") (pinfunction "IO_L44P_GCLK21_3_P15") (pintype "bidirectional"))
      (node (ref "SDRAM") (pin "20") (pinfunction "BA0_20") (pintype "bidirectional"))
    )
    (net (code "86") (name "/SDR_BA1") (class "Default")
      (node (ref "FPGA") (pin "P14") (pinfunction "IO_L44N_GCLK20_3_P14") (pintype "bidirectional"))
      (node (ref "SDRAM") (pin "21") (pinfunction "BA1_21") (pintype "bidirectional"))
    )
    (net (code "87") (name "/SDR_CAS") (class "Default")
      (node (ref "FPGA") (pin "P21") (pinfunction "IO_L42N_GCLK24_3_P21") (pintype "bidirectional"))
      (node (ref "SDRAM") (pin "17") (pinfunction "CAS_17") (pintype "bidirectional"))
    )
    (net (code "88") (name "/SDR_CKE") (class "Default")
      (node (ref "FPGA") (pin "P139") (pinfunction "IO_L03N_0_P139") (pintype "bidirectional"))
      (node (ref "SDRAM") (pin "37") (pinfunction "CKE_37") (pintype "bidirectional"))
    )
    (net (code "89") (name "/SDR_CLK") (class "Default")
      (node (ref "FPGA") (pin "P140") (pinfunction "IO_L03P_0_P140") (pintype "bidirectional"))
      (node (ref "SDRAM") (pin "38") (pinfunction "CLK_38") (pintype "bidirectional"))
    )
    (net (code "90") (name "/SDR_CS") (class "Default")
      (node (ref "FPGA") (pin "P16") (pinfunction "IO_L43N_GCLK22_IRDY2_3_P16") (pintype "bidirectional"))
      (node (ref "SDRAM") (pin "19") (pinfunction "CS_19") (pintype "bidirectional"))
    )
    (net (code "91") (name "/SDR_DQ0") (class "Default")
      (node (ref "FPGA") (pin "P34") (pinfunction "IO_L01N_VREF_3_P34") (pintype "bidirectional"))
      (node (ref "SDRAM") (pin "2") (pinfunction "DQ0_2") (pintype "bidirectional"))
    )
    (net (code "92") (name "/SDR_DQ1") (class "Default")
      (node (ref "FPGA") (pin "P33") (pinfunction "IO_L02P_3_P33") (pintype "bidirectional"))
      (node (ref "SDRAM") (pin "4") (pinfunction "DQ1_4") (pintype "bidirectional"))
    )
    (net (code "93") (name "/SDR_DQ2") (class "Default")
      (node (ref "FPGA") (pin "P32") (pinfunction "IO_L02N_3_P32") (pintype "bidirectional"))
      (node (ref "SDRAM") (pin "5") (pinfunction "DQ2_5") (pintype "bidirectional"))
    )
    (net (code "94") (name "/SDR_DQ3") (class "Default")
      (node (ref "FPGA") (pin "P30") (pinfunction "IO_L36P_3_P30") (pintype "bidirectional"))
      (node (ref "SDRAM") (pin "7") (pinfunction "DQ3_7") (pintype "bidirectional"))
    )
    (net (code "95") (name "/SDR_DQ4") (class "Default")
      (node (ref "FPGA") (pin "P29") (pinfunction "IO_L36N_3_P29") (pintype "bidirectional"))
      (node (ref "SDRAM") (pin "8") (pinfunction "DQ4_8") (pintype "bidirectional"))
    )
    (net (code "96") (name "/SDR_DQ5") (class "Default")
      (node (ref "FPGA") (pin "P27") (pinfunction "IO_L37P_3_P27") (pintype "bidirectional"))
      (node (ref "SDRAM") (pin "10") (pinfunction "DQ5_10") (pintype "bidirectional"))
    )
    (net (code "97") (name "/SDR_DQ6") (class "Default")
      (node (ref "FPGA") (pin "P26") (pinfunction "IO_L37N_3_P26") (pintype "bidirectional"))
      (node (ref "SDRAM") (pin "11") (pinfunction "DQ6_11") (pintype "bidirectional"))
    )
    (net (code "98") (name "/SDR_DQ7") (class "Default")
      (node (ref "FPGA") (pin "P24") (pinfunction "IO_L41P_GCLK27_3_P24") (pintype "bidirectional"))
      (node (ref "SDRAM") (pin "13") (pinfunction "DQ7_13") (pintype "bidirectional"))
    )
    (net (code "99") (name "/SDR_DQ8") (class "Default")
      (node (ref "FPGA") (pin "P142") (pinfunction "IO_L02P_0_P142") (pintype "bidirectional"))
      (node (ref "SDRAM") (pin "42") (pinfunction "DQ8_42") (pintype "bidirectional"))
    )
    (net (code "100") (name "/SDR_DQ9") (class "Default")
      (node (ref "FPGA") (pin "P143") (pinfunction "IO_L01N_VREF_0_P143") (pintype "bidirectional"))
      (node (ref "SDRAM") (pin "44") (pinfunction "DQ9_44") (pintype "bidirectional"))
    )
    (net (code "101") (name "/SDR_DQ10") (class "Default")
      (node (ref "FPGA") (pin "P144") (pinfunction "IO_L01P_HSWAPEN_0_P144") (pintype "bidirectional"))
      (node (ref "SDRAM") (pin "45") (pinfunction "DQ10_45") (pintype "bidirectional"))
    )
    (net (code "102") (name "/SDR_DQ11") (class "Default")
      (node (ref "FPGA") (pin "P1") (pinfunction "IO_L83N_VREF_3_P1") (pintype "bidirectional"))
      (node (ref "SDRAM") (pin "47") (pinfunction "DQ11_47") (pintype "bidirectional"))
    )
    (net (code "103") (name "/SDR_DQ12") (class "Default")
      (node (ref "FPGA") (pin "P2") (pinfunction "IO_L83P_3_P2") (pintype "bidirectional"))
      (node (ref "SDRAM") (pin "48") (pinfunction "DQ12_48") (pintype "bidirectional"))
    )
    (net (code "104") (name "/SDR_DQ13") (class "Default")
      (node (ref "FPGA") (pin "P5") (pinfunction "IO_L52N_3_P5") (pintype "bidirectional"))
      (node (ref "SDRAM") (pin "50") (pinfunction "DQ13_50") (pintype "bidirectional"))
    )
    (net (code "105") (name "/SDR_DQ14") (class "Default")
      (node (ref "FPGA") (pin "P6") (pinfunction "IO_L52P_3_P6") (pintype "bidirectional"))
      (node (ref "SDRAM") (pin "51") (pinfunction "DQ14_51") (pintype "bidirectional"))
    )
    (net (code "106") (name "/SDR_DQ15") (class "Default")
      (node (ref "FPGA") (pin "P7") (pinfunction "IO_L51N_3_P7") (pintype "bidirectional"))
      (node (ref "SDRAM") (pin "53") (pinfunction "DQ15_53") (pintype "bidirectional"))
    )
    (net (code "107") (name "/SDR_DQMH") (class "Default")
      (node (ref "FPGA") (pin "P141") (pinfunction "IO_L02N_0_P141") (pintype "bidirectional"))
      (node (ref "SDRAM") (pin "39") (pinfunction "DQMH_39") (pintype "bidirectional"))
    )
    (net (code "108") (name "/SDR_DQML") (class "Default")
      (node (ref "FPGA") (pin "P23") (pinfunction "IO_L41N_GCLK26_3_P23") (pintype "bidirectional"))
      (node (ref "SDRAM") (pin "15") (pinfunction "DQML_15") (pintype "bidirectional"))
    )
    (net (code "109") (name "/SDR_RAS") (class "Default")
      (node (ref "FPGA") (pin "P17") (pinfunction "IO_L43P_GCLK23_3_P17") (pintype "bidirectional"))
      (node (ref "SDRAM") (pin "18") (pinfunction "RAS_18") (pintype "bidirectional"))
    )
    (net (code "110") (name "/SDR_WE") (class "Default")
      (node (ref "FPGA") (pin "P22") (pinfunction "IO_L42P_GCLK25_TRDY2_3_P22") (pintype "bidirectional"))
      (node (ref "SDRAM") (pin "16") (pinfunction "WE_16") (pintype "bidirectional"))
    )
    (net (code "111") (name "/SD_CLK") (class "Default")
      (node (ref "MCU") (pin "80") (pinfunction "SDIO_CLK_80") (pintype "bidirectional"))
      (node (ref "MICROSD") (pin "5") (pinfunction "SCK_5") (pintype "bidirectional"))
      (node (ref "R38") (pin "2") (pinfunction "2_2") (pintype "passive"))
    )
    (net (code "112") (name "/SD_CMD") (class "Default")
      (node (ref "MCU") (pin "83") (pinfunction "SDIO_CMD_83") (pintype "bidirectional"))
      (node (ref "MICROSD") (pin "3") (pinfunction "DI_3") (pintype "bidirectional"))
      (node (ref "R41") (pin "1") (pinfunction "1_1") (pintype "passive"))
    )
    (net (code "113") (name "/SD_D0") (class "Default")
      (node (ref "MCU") (pin "65") (pinfunction "SDIO_D0_65") (pintype "bidirectional"))
      (node (ref "MICROSD") (pin "7") (pinfunction "DO_7") (pintype "bidirectional"))
      (node (ref "R42") (pin "1") (pinfunction "1_1") (pintype "passive"))
    )
    (net (code "114") (name "/SD_D1") (class "Default")
      (node (ref "MCU") (pin "66") (pinfunction "SDIO_D1_66") (pintype "bidirectional"))
      (node (ref "MICROSD") (pin "8") (pinfunction "RSV_8") (pintype "bidirectional"))
      (node (ref "R43") (pin "1") (pinfunction "1_1") (pintype "passive"))
    )
    (net (code "115") (name "/SD_D2") (class "Default")
      (node (ref "MCU") (pin "78") (pinfunction "SDIO_D2_78") (pintype "bidirectional"))
      (node (ref "MICROSD") (pin "1") (pinfunction "NC_1") (pintype "bidirectional"))
      (node (ref "R39") (pin "1") (pinfunction "1_1") (pintype "passive"))
    )
    (net (code "116") (name "/SD_D3") (class "Default")
      (node (ref "MCU") (pin "79") (pinfunction "SDIO_D3_79") (pintype "bidirectional"))
      (node (ref "MICROSD") (pin "2") (pinfunction "CS_2") (pintype "bidirectional"))
      (node (ref "R40") (pin "1") (pinfunction "1_1") (pintype "passive"))
    )
    (net (code "117") (name "/SD_DETECT") (class "Default")
      (node (ref "MCU") (pin "64") (pinfunction "PC7_64") (pintype "bidirectional"))
      (node (ref "MICROSD") (pin "CD1") (pinfunction "SHIELD_CD1") (pintype "bidirectional"))
      (node (ref "R24") (pin "1") (pinfunction "1_1") (pintype "passive"))
    )
    (net (code "118") (name "/SPI_MISO") (class "Default")
      (node (ref "FPGA") (pin "P67") (pinfunction "IO_L02P_CMPCLK_2_P67") (pintype "bidirectional"))
      (node (ref "MCU") (pin "31") (pinfunction "SPI1_MISO_31") (pintype "bidirectional"))
    )
    (net (code "119") (name "/TCK{slash}SWCLK") (class "Default")
      (node (ref "JTAG") (pin "9") (pinfunction "9_9") (pintype "passive"))
      (node (ref "MCU") (pin "76") (pinfunction "TCK/SWCLK_76") (pintype "bidirectional"))
    )
    (net (code "120") (name "/TDI") (class "Default")
      (node (ref "JTAG") (pin "5") (pinfunction "5_5") (pintype "passive"))
      (node (ref "MCU") (pin "77") (pinfunction "TDI_77") (pintype "bidirectional"))
    )
    (net (code "121") (name "/TDO{slash}SWO") (class "Default")
      (node (ref "JTAG") (pin "13") (pinfunction "13_13") (pintype "passive"))
      (node (ref "MCU") (pin "89") (pinfunction "TDO/SWO_89") (pintype "bidirectional"))
    )
    (net (code "122") (name "/TMDS_CLKN") (class "Default")
      (node (ref "FPGA") (pin "P116") (pinfunction "IO_L64N_SCP4_0_P116") (pintype "bidirectional"))
      (node (ref "R27") (pin "1") (pinfunction "1_1") (pintype "passive"))
      (node (ref "U$2") (pin "P12") (pinfunction "TMDS_CLKN_P12") (pintype "bidirectional"))
    )
    (net (code "123") (name "/TMDS_CLKP") (class "Default")
      (node (ref "FPGA") (pin "P117") (pinfunction "IO_L64P_SCP5_0_P117") (pintype "bidirectional"))
      (node (ref "R27") (pin "2") (pinfunction "1_2") (pintype "passive"))
      (node (ref "U$2") (pin "P10") (pinfunction "TMDS_CLKP_P10") (pintype "bidirectional"))
    )
    (net (code "124") (name "/TMDS_D0N") (class "Default")
      (node (ref "FPGA") (pin "P118") (pinfunction "IO_L63N_SCP6_0_P118") (pintype "bidirectional"))
      (node (ref "R27") (pin "3") (pinfunction "1_3") (pintype "passive"))
      (node (ref "U$2") (pin "P9") (pinfunction "TMDS_D0N_P9") (pintype "bidirectional"))
    )
    (net (code "125") (name "/TMDS_D0P") (class "Default")
      (node (ref "FPGA") (pin "P119") (pinfunction "IO_L63P_SCP7_0_P119") (pintype "bidirectional"))
      (node (ref "R27") (pin "4") (pinfunction "1_4") (pintype "passive"))
      (node (ref "U$2") (pin "P7") (pinfunction "TMDS_D0P_P7") (pintype "bidirectional"))
    )
    (net (code "126") (name "/TMDS_D1N") (class "Default")
      (node (ref "FPGA") (pin "P120") (pinfunction "IO_L62N_VREF_0_P120") (pintype "bidirectional"))
      (node (ref "R28") (pin "1") (pinfunction "1_1") (pintype "passive"))
      (node (ref "U$2") (pin "P6") (pinfunction "TMDS_D1N_P6") (pintype "bidirectional"))
    )
    (net (code "127") (name "/TMDS_D1P") (class "Default")
      (node (ref "FPGA") (pin "P121") (pinfunction "IO_L62P_0_P121") (pintype "bidirectional"))
      (node (ref "R28") (pin "2") (pinfunction "1_2") (pintype "passive"))
      (node (ref "U$2") (pin "P4") (pinfunction "TMDS_D1P_P4") (pintype "bidirectional"))
    )
    (net (code "128") (name "/TMDS_D2N") (class "Default")
      (node (ref "FPGA") (pin "P123") (pinfunction "IO_L37N_GCLK12_0_P123") (pintype "bidirectional"))
      (node (ref "R28") (pin "3") (pinfunction "1_3") (pintype "passive"))
      (node (ref "U$2") (pin "P3") (pinfunction "TMDS_D2N_P3") (pintype "bidirectional"))
    )
    (net (code "129") (name "/TMDS_D2P") (class "Default")
      (node (ref "FPGA") (pin "P124") (pinfunction "IO_L37P_GCLK13_0_P124") (pintype "bidirectional"))
      (node (ref "R28") (pin "4") (pinfunction "1_4") (pintype "passive"))
      (node (ref "U$2") (pin "P1") (pinfunction "TMDS_D2P_P1") (pintype "bidirectional"))
    )
    (net (code "130") (name "/TMS{slash}SWDIO") (class "Default")
      (node (ref "JTAG") (pin "7") (pinfunction "7_7") (pintype "passive"))
      (node (ref "MCU") (pin "72") (pinfunction "TMS/SWDIO_72") (pintype "bidirectional"))
    )
    (net (code "131") (name "/USB_EN") (class "Default")
      (node (ref "MCU") (pin "69") (pinfunction "USB_EN_ID_69") (pintype "bidirectional"))
      (node (ref "MIC5219-5.0YM5") (pin "3") (pinfunction "EN_3") (pintype "input"))
      (node (ref "R25") (pin "1") (pinfunction "1_1") (pintype "passive"))
    )
    (net (code "132") (name "/USB_VBUS") (class "Default")
      (node (ref "C3") (pin "1") (pinfunction "1_1") (pintype "passive"))
      (node (ref "C4") (pin "1") (pinfunction "1_1") (pintype "passive"))
      (node (ref "MCU") (pin "68") (pinfunction "USB_VBUS_68") (pintype "bidirectional"))
      (node (ref "MIC5219-5.0YM5") (pin "5") (pinfunction "OUT_5") (pintype "passive"))
      (node (ref "X1") (pin "VBUS") (pinfunction "VBUS_VBUS") (pintype "bidirectional"))
    )
    (net (code "133") (name "/VSYNC") (class "Default")
      (node (ref "FPGA") (pin "P66") (pinfunction "IO_L02N_CMPMOSI_2_P66") (pintype "bidirectional"))
      (node (ref "MCU") (pin "35") (pinfunction "PB0_35") (pintype "bidirectional"))
    )
    (net (code "134") (name "/{slash}TRST") (class "Default")
      (node (ref "JTAG") (pin "3") (pinfunction "3_3") (pintype "passive"))
      (node (ref "MCU") (pin "90") (pinfunction "TRST_90") (pintype "bidirectional"))
    )
    (net (code "135") (name "GND") (class "Default")
      (node (ref "C1") (pin "1") (pinfunction "1_1") (pintype "passive"))
      (node (ref "C10") (pin "2") (pinfunction "2_2") (pintype "passive"))
      (node (ref "C11") (pin "2") (pinfunction "2_2") (pintype "passive"))
      (node (ref "C12") (pin "2") (pinfunction "2_2") (pintype "passive"))
      (node (ref "C13") (pin "2") (pinfunction "2_2") (pintype "passive"))
      (node (ref "C14") (pin "2") (pinfunction "2_2") (pintype "passive"))
      (node (ref "C15") (pin "2") (pinfunction "2_2") (pintype "passive"))
      (node (ref "C16") (pin "2") (pinfunction "2_2") (pintype "passive"))
      (node (ref "C17") (pin "2") (pinfunction "2_2") (pintype "passive"))
      (node (ref "C18") (pin "2") (pinfunction "2_2") (pintype "passive"))
      (node (ref "C19") (pin "2") (pinfunction "2_2") (pintype "passive"))
      (node (ref "C2") (pin "2") (pinfunction "2_2") (pintype "passive"))
      (node (ref "C20") (pin "1") (pinfunction "1_1") (pintype "passive"))
      (node (ref "C21") (pin "2") (pinfunction "2_2") (pintype "passive"))
      (node (ref "C22") (pin "2") (pinfunction "2_2") (pintype "passive"))
      (node (ref "C23") (pin "2") (pinfunction "2_2") (pintype "passive"))
      (node (ref "C24") (pin "2") (pinfunction "2_2") (pintype "passive"))
      (node (ref "C25") (pin "2") (pinfunction "2_2") (pintype "passive"))
      (node (ref "C26") (pin "2") (pinfunction "2_2") (pintype "passive"))
      (node (ref "C27") (pin "2") (pinfunction "2_2") (pintype "passive"))
      (node (ref "C28") (pin "2") (pinfunction "2_2") (pintype "passive"))
      (node (ref "C29") (pin "2") (pinfunction "2_2") (pintype "passive"))
      (node (ref "C3") (pin "2") (pinfunction "2_2") (pintype "passive"))
      (node (ref "C30") (pin "2") (pinfunction "2_2") (pintype "passive"))
      (node (ref "C31") (pin "2") (pinfunction "2_2") (pintype "passive"))
      (node (ref "C32") (pin "2") (pinfunction "2_2") (pintype "passive"))
      (node (ref "C33") (pin "2") (pinfunction "2_2") (pintype "passive"))
      (node (ref "C34") (pin "2") (pinfunction "2_2") (pintype "passive"))
      (node (ref "C35") (pin "2") (pinfunction "2_2") (pintype "passive"))
      (node (ref "C36") (pin "2") (pinfunction "2_2") (pintype "passive"))
      (node (ref "C37") (pin "2") (pinfunction "2_2") (pintype "passive"))
      (node (ref "C38") (pin "2") (pinfunction "2_2") (pintype "passive"))
      (node (ref "C39") (pin "2") (pinfunction "2_2") (pintype "passive"))
      (node (ref "C4") (pin "2") (pinfunction "2_2") (pintype "passive"))
      (node (ref "C40") (pin "2") (pinfunction "2_2") (pintype "passive"))
      (node (ref "C41") (pin "2") (pinfunction "2_2") (pintype "passive"))
      (node (ref "C42") (pin "2") (pinfunction "2_2") (pintype "passive"))
      (node (ref "C43") (pin "2") (pinfunction "2_2") (pintype "passive"))
      (node (ref "C44") (pin "2") (pinfunction "2_2") (pintype "passive"))
      (node (ref "C45") (pin "2") (pinfunction "-_2") (pintype "passive"))
      (node (ref "C46") (pin "2") (pinfunction "-_2") (pintype "passive"))
      (node (ref "C47") (pin "2") (pinfunction "-_2") (pintype "passive"))
      (node (ref "C48") (pin "2") (pinfunction "-_2") (pintype "passive"))
      (node (ref "C49") (pin "2") (pinfunction "2_2") (pintype "passive"))
      (node (ref "C5") (pin "2") (pinfunction "2_2") (pintype "passive"))
      (node (ref "C6") (pin "2") (pinfunction "2_2") (pintype "passive"))
      (node (ref "C7") (pin "2") (pinfunction "2_2") (pintype "passive"))
      (node (ref "C8") (pin "2") (pinfunction "2_2") (pintype "passive"))
      (node (ref "C9") (pin "2") (pinfunction "2_2") (pintype "passive"))
      (node (ref "ETH_PHY") (pin "15") (pinfunction "AGND1_15") (pintype "bidirectional"))
      (node (ref "ETH_PHY") (pin "19") (pinfunction "AGND2_19") (pintype "bidirectional"))
      (node (ref "ETH_PHY") (pin "35") (pinfunction "IOGND_35") (pintype "bidirectional"))
      (node (ref "ETH_PHY") (pin "36") (pinfunction "DGND_36") (pintype "bidirectional"))
      (node (ref "ETH_PHY") (pin "47") (pinfunction "IOGND2_47") (pintype "bidirectional"))
      (node (ref "FPGA") (pin "P108") (pinfunction "GND_P108") (pintype "power_in"))
      (node (ref "FPGA") (pin "P113") (pinfunction "GND_P113") (pintype "power_in"))
      (node (ref "FPGA") (pin "P13") (pinfunction "GND_P13") (pintype "power_in"))
      (node (ref "FPGA") (pin "P130") (pinfunction "GND_P130") (pintype "power_in"))
      (node (ref "FPGA") (pin "P136") (pinfunction "GND_P136") (pintype "power_in"))
      (node (ref "FPGA") (pin "P25") (pinfunction "GND_P25") (pintype "power_in"))
      (node (ref "FPGA") (pin "P3") (pinfunction "GND_P3") (pintype "power_in"))
      (node (ref "FPGA") (pin "P49") (pinfunction "GND_P49") (pintype "power_in"))
      (node (ref "FPGA") (pin "P54") (pinfunction "GND_P54") (pintype "power_in"))
      (node (ref "FPGA") (pin "P68") (pinfunction "GND_P68") (pintype "power_in"))
      (node (ref "FPGA") (pin "P73") (pinfunction "SUSPEND_P73") (pintype "input"))
      (node (ref "FPGA") (pin "P77") (pinfunction "GND_P77") (pintype "power_in"))
      (node (ref "FPGA") (pin "P91") (pinfunction "GND_P91") (pintype "power_in"))
      (node (ref "FPGA") (pin "P96") (pinfunction "GND_P96") (pintype "power_in"))
      (node (ref "FPGA_JTAG") (pin "11") (pinfunction "11_11") (pintype "passive"))
      (node (ref "FPGA_JTAG") (pin "13") (pinfunction "13_13") (pintype "passive"))
      (node (ref "FPGA_JTAG") (pin "3") (pinfunction "3_3") (pintype "passive"))
      (node (ref "FPGA_JTAG") (pin "5") (pinfunction "5_5") (pintype "passive"))
      (node (ref "FPGA_JTAG") (pin "7") (pinfunction "7_7") (pintype "passive"))
      (node (ref "FPGA_JTAG") (pin "9") (pinfunction "9_9") (pintype "passive"))
      (node (ref "J2") (pin "GND") (pinfunction "GND_GND") (pintype "bidirectional"))
      (node (ref "J2") (pin "GNDBREAK") (pinfunction "GNDBREAK_GNDBREAK") (pintype "bidirectional"))
      (node (ref "JTAG") (pin "10") (pinfunction "10_10") (pintype "passive"))
      (node (ref "JTAG") (pin "12") (pinfunction "12_12") (pintype "passive"))
      (node (ref "JTAG") (pin "14") (pinfunction "14_14") (pintype "passive"))
      (node (ref "JTAG") (pin "16") (pinfunction "16_16") (pintype "passive"))
      (node (ref "JTAG") (pin "18") (pinfunction "18_18") (pintype "passive"))
      (node (ref "JTAG") (pin "20") (pinfunction "20_20") (pintype "passive"))
      (node (ref "JTAG") (pin "4") (pinfunction "4_4") (pintype "passive"))
      (node (ref "JTAG") (pin "6") (pinfunction "6_6") (pintype "passive"))
      (node (ref "JTAG") (pin "8") (pinfunction "8_8") (pintype "passive"))
      (node (ref "LED_L_EYE") (pin "K") (pinfunction "C_K") (pintype "passive"))
      (node (ref "LED_R_EYE") (pin "K") (pinfunction "C_K") (pintype "passive"))
      (node (ref "MCU") (pin "10") (pinfunction "VSS_10") (pintype "bidirectional"))
      (node (ref "MCU") (pin "20") (pinfunction "VSSA_20") (pintype "bidirectional"))
      (node (ref "MCU") (pin "27") (pinfunction "VSS_27") (pintype "bidirectional"))
      (node (ref "MCU") (pin "74") (pinfunction "VSS_74") (pintype "bidirectional"))
      (node (ref "MCU") (pin "99") (pinfunction "VSS_99") (pintype "bidirectional"))
      (node (ref "MIC5219-3.3YM5_1") (pin "2") (pinfunction "GND_2") (pintype "input"))
      (node (ref "MIC5219-3.3YM5_2") (pin "2") (pinfunction "GND_2") (pintype "input"))
      (node (ref "MIC5219-5.0YM1") (pin "2") (pinfunction "GND_2") (pintype "input"))
      (node (ref "MIC5219-5.0YM5") (pin "2") (pinfunction "GND_2") (pintype "input"))
      (node (ref "MICROSD") (pin "6") (pinfunction "GND_6") (pintype "bidirectional"))
      (node (ref "MICROSD") (pin "GND1") (pinfunction "SHIELD_GND1") (pintype "bidirectional"))
      (node (ref "MICROSD") (pin "GND3") (pinfunction "SHIELD_GND3") (pintype "bidirectional"))
      (node (ref "NCP565ST12T3G") (pin "1") (pinfunction "ADJ_1") (pintype "input"))
      (node (ref "OSC_50M") (pin "2") (pinfunction "GND_2") (pintype "bidirectional"))
      (node (ref "R1") (pin "2") (pinfunction "2_2") (pintype "passive"))
      (node (ref "R16") (pin "1") (pinfunction "1_1") (pintype "passive"))
      (node (ref "R18") (pin "1") (pinfunction "1_1") (pintype "passive"))
      (node (ref "R2") (pin "2") (pinfunction "2_2") (pintype "passive"))
      (node (ref "R20") (pin "1") (pinfunction "1_1") (pintype "passive"))
      (node (ref "R3") (pin "2") (pinfunction "2_2") (pintype "passive"))
      (node (ref "R38") (pin "1") (pinfunction "1_1") (pintype "passive"))
      (node (ref "RESET") (pin "1") (pinfunction "1_1") (pintype "passive"))
      (node (ref "RESET") (pin "2") (pinfunction "2_2") (pintype "passive"))
      (node (ref "RJ45") (pin "8") (pinfunction "SHIELD_8") (pintype "bidirectional"))
      (node (ref "SDRAM") (pin "12") (pinfunction "VSSQ2_12") (pintype "bidirectional"))
      (node (ref "SDRAM") (pin "28") (pinfunction "VSS1_28") (pintype "bidirectional"))
      (node (ref "SDRAM") (pin "41") (pinfunction "VSS2_41") (pintype "bidirectional"))
      (node (ref "SDRAM") (pin "46") (pinfunction "VSSQ3_46") (pintype "bidirectional"))
      (node (ref "SDRAM") (pin "52") (pinfunction "VSSQ4_52") (pintype "bidirectional"))
      (node (ref "SDRAM") (pin "54") (pinfunction "VSS3_54") (pintype "bidirectional"))
      (node (ref "SDRAM") (pin "6") (pinfunction "VSSQ1_6") (pintype "bidirectional"))
      (node (ref "U$2") (pin "P11") (pinfunction "TMDS_CLK_SHLD_P11") (pintype "bidirectional"))
      (node (ref "U$2") (pin "P17") (pinfunction "GND_P17") (pintype "bidirectional"))
      (node (ref "U$2") (pin "P2") (pinfunction "TMDS_D2_SHLD_P2") (pintype "bidirectional"))
      (node (ref "U$2") (pin "P5") (pinfunction "TMDS_D1_SHLD_P5") (pintype "bidirectional"))
      (node (ref "U$2") (pin "P8") (pinfunction "TMDS_D0_SHLD_P8") (pintype "bidirectional"))
      (node (ref "U$3") (pin "5") (pinfunction "GND_5") (pintype "bidirectional"))
      (node (ref "U$4") (pin "L") (pinfunction "L_L") (pintype "bidirectional"))
      (node (ref "U$4") (pin "R") (pinfunction "R_R") (pintype "bidirectional"))
      (node (ref "X1") (pin "GND") (pinfunction "GND_GND") (pintype "bidirectional"))
    )
    (net (code "136") (name "Net-(D1-PadA)") (class "Default")
      (node (ref "D1") (pin "A") (pinfunction "A_A") (pintype "passive"))
      (node (ref "J2") (pin "PWR") (pinfunction "PWR_PWR") (pintype "bidirectional"))
    )
    (net (code "137") (name "Net-(ETH_PHY-LED_SPEED{slash}AN1)") (class "Default")
      (node (ref "ETH_PHY") (pin "27") (pinfunction "LED_SPEED/AN1_27") (pintype "bidirectional"))
      (node (ref "R12") (pin "1") (pinfunction "1_1") (pintype "passive"))
    )
    (net (code "138") (name "Net-(ETH_PHY-RBIAS)") (class "Default")
      (node (ref "ETH_PHY") (pin "24") (pinfunction "RBIAS_24") (pintype "bidirectional"))
      (node (ref "R16") (pin "2") (pinfunction "2_2") (pintype "passive"))
    )
    (net (code "139") (name "Net-(ETH_PHY-RD+)") (class "Default")
      (node (ref "ETH_PHY") (pin "14") (pinfunction "RD+_14") (pintype "bidirectional"))
      (node (ref "R10") (pin "1") (pinfunction "1_1") (pintype "passive"))
      (node (ref "RJ45") (pin "1") (pinfunction "RD+_1") (pintype "bidirectional"))
    )
    (net (code "140") (name "Net-(ETH_PHY-RD-)") (class "Default")
      (node (ref "ETH_PHY") (pin "13") (pinfunction "RD-_13") (pintype "bidirectional"))
      (node (ref "R9") (pin "1") (pinfunction "1_1") (pintype "passive"))
      (node (ref "RJ45") (pin "3") (pinfunction "RD-_3") (pintype "bidirectional"))
    )
    (net (code "141") (name "Net-(ETH_PHY-TD+)") (class "Default")
      (node (ref "ETH_PHY") (pin "17") (pinfunction "TD+_17") (pintype "bidirectional"))
      (node (ref "R6") (pin "1") (pinfunction "1_1") (pintype "passive"))
      (node (ref "RJ45") (pin "4") (pinfunction "TD+_4") (pintype "bidirectional"))
    )
    (net (code "142") (name "Net-(ETH_PHY-TD-)") (class "Default")
      (node (ref "ETH_PHY") (pin "16") (pinfunction "TD-_16") (pintype "bidirectional"))
      (node (ref "R5") (pin "1") (pinfunction "1_1") (pintype "passive"))
      (node (ref "RJ45") (pin "6") (pinfunction "TD-_6") (pintype "bidirectional"))
    )
    (net (code "143") (name "Net-(ETH_PHY-TXD_3)") (class "Default")
      (node (ref "ETH_PHY") (pin "6") (pinfunction "TXD_3_6") (pintype "bidirectional"))
      (node (ref "R18") (pin "2") (pinfunction "2_2") (pintype "passive"))
    )
    (net (code "144") (name "Net-(FPGAC-IO_L01P_CCLK_2)") (class "Default")
      (node (ref "FPGA") (pin "P70") (pinfunction "IO_L01P_CCLK_2_P70") (pintype "bidirectional"))
      (node (ref "R29") (pin "1") (pinfunction "1_1") (pintype "passive"))
    )
    (net (code "145") (name "Net-(LED_L_EYE-PadA)") (class "Default")
      (node (ref "LED_L_EYE") (pin "A") (pinfunction "A_A") (pintype "passive"))
      (node (ref "R36") (pin "1") (pinfunction "1_1") (pintype "passive"))
    )
    (net (code "146") (name "Net-(LED_R_EYE-PadA)") (class "Default")
      (node (ref "LED_R_EYE") (pin "A") (pinfunction "A_A") (pintype "passive"))
      (node (ref "R37") (pin "1") (pinfunction "1_1") (pintype "passive"))
    )
    (net (code "147") (name "Net-(MCUE-USB_FS_DM)") (class "Default")
      (node (ref "MCU") (pin "70") (pinfunction "USB_FS_DM_70") (pintype "bidirectional"))
      (node (ref "R22") (pin "2") (pinfunction "2_2") (pintype "passive"))
    )
    (net (code "148") (name "Net-(MCUE-USB_FS_DP)") (class "Default")
      (node (ref "MCU") (pin "71") (pinfunction "USB_FS_DP_71") (pintype "bidirectional"))
      (node (ref "R21") (pin "2") (pinfunction "2_2") (pintype "passive"))
    )
    (net (code "149") (name "Net-(MCUH-OSC_IN)") (class "Default")
      (node (ref "C18") (pin "1") (pinfunction "1_1") (pintype "passive"))
      (node (ref "MCU") (pin "12") (pinfunction "OSC_IN_12") (pintype "bidirectional"))
      (node (ref "Y1") (pin "2") (pinfunction "2_2") (pintype "passive"))
    )
    (net (code "150") (name "Net-(MCUH-OSC_OUT)") (class "Default")
      (node (ref "C19") (pin "1") (pinfunction "1_1") (pintype "passive"))
      (node (ref "MCU") (pin "13") (pinfunction "OSC_OUT_13") (pintype "bidirectional"))
      (node (ref "Y1") (pin "1") (pinfunction "1_1") (pintype "passive"))
    )
    (net (code "151") (name "Net-(MIC5219-3.3YM5_1-BP)") (class "Default")
      (node (ref "C7") (pin "1") (pinfunction "1_1") (pintype "passive"))
      (node (ref "MIC5219-3.3YM5_1") (pin "4") (pinfunction "BP_4") (pintype "input"))
    )
    (net (code "152") (name "Net-(MIC5219-3.3YM5_1-EN)") (class "Default")
      (node (ref "MIC5219-3.3YM5_1") (pin "3") (pinfunction "EN_3") (pintype "input"))
      (node (ref "R7") (pin "1") (pinfunction "1_1") (pintype "passive"))
    )
    (net (code "153") (name "Net-(MIC5219-3.3YM5_2-BP)") (class "Default")
      (node (ref "C11") (pin "1") (pinfunction "1_1") (pintype "passive"))
      (node (ref "MIC5219-3.3YM5_2") (pin "4") (pinfunction "BP_4") (pintype "input"))
    )
    (net (code "154") (name "Net-(MIC5219-3.3YM5_2-EN)") (class "Default")
      (node (ref "MIC5219-3.3YM5_2") (pin "3") (pinfunction "EN_3") (pintype "input"))
      (node (ref "R8") (pin "1") (pinfunction "1_1") (pintype "passive"))
    )
    (net (code "155") (name "Net-(MIC5219-5.0YM1-BP)") (class "Default")
      (node (ref "C28") (pin "1") (pinfunction "1_1") (pintype "passive"))
      (node (ref "MIC5219-5.0YM1") (pin "4") (pinfunction "BP_4") (pintype "input"))
    )
    (net (code "156") (name "Net-(MIC5219-5.0YM1-EN)") (class "Default")
      (node (ref "MIC5219-5.0YM1") (pin "3") (pinfunction "EN_3") (pintype "input"))
      (node (ref "R23") (pin "1") (pinfunction "1_1") (pintype "passive"))
    )
    (net (code "157") (name "Net-(MIC5219-5.0YM5-BP)") (class "Default")
      (node (ref "C2") (pin "1") (pinfunction "1_1") (pintype "passive"))
      (node (ref "MIC5219-5.0YM5") (pin "4") (pinfunction "BP_4") (pintype "input"))
    )
    (net (code "158") (name "Net-(OSC_50M-EN)") (class "Default")
      (node (ref "OSC_50M") (pin "1") (pinfunction "EN_1") (pintype "bidirectional"))
      (node (ref "R26") (pin "1") (pinfunction "1_1") (pintype "passive"))
    )
    (net (code "159") (name "Net-(R21-Pad1)") (class "Default")
      (node (ref "R21") (pin "1") (pinfunction "1_1") (pintype "passive"))
      (node (ref "X1") (pin "D+") (pinfunction "D+_D+") (pintype "bidirectional"))
    )
    (net (code "160") (name "Net-(R22-Pad1)") (class "Default")
      (node (ref "R22") (pin "1") (pinfunction "1_1") (pintype "passive"))
      (node (ref "X1") (pin "D-") (pinfunction "D-_D-") (pintype "bidirectional"))
    )
    (net (code "161") (name "Net-(RJ45-GLED+)") (class "Default")
      (node (ref "R15") (pin "2") (pinfunction "2_2") (pintype "passive"))
      (node (ref "RJ45") (pin "10") (pinfunction "GLED+_10") (pintype "bidirectional"))
    )
    (net (code "162") (name "Net-(RJ45-YLED+)") (class "Default")
      (node (ref "R14") (pin "1") (pinfunction "1_1") (pintype "passive"))
      (node (ref "RJ45") (pin "12") (pinfunction "YLED+_12") (pintype "bidirectional"))
    )
    (net (code "163") (name "Net-(U$2-DETECT)") (class "Default")
      (node (ref "R19") (pin "2") (pinfunction "2_2") (pintype "passive"))
      (node (ref "U$2") (pin "P19") (pinfunction "DETECT_P19") (pintype "bidirectional"))
    )
    (net (code "164") (name "Net-(U$3-SCLA)") (class "Default")
      (node (ref "R32") (pin "1") (pinfunction "1_1") (pintype "passive"))
      (node (ref "U$3") (pin "2") (pinfunction "SCLA_2") (pintype "bidirectional"))
    )
    (net (code "165") (name "Net-(U$3-SDAA)") (class "Default")
      (node (ref "R33") (pin "1") (pinfunction "1_1") (pintype "passive"))
      (node (ref "U$3") (pin "3") (pinfunction "SDAA_3") (pintype "bidirectional"))
    )
    (net (code "166") (name "V+") (class "Default")
      (node (ref "C10") (pin "1") (pinfunction "1_1") (pintype "passive"))
      (node (ref "C14") (pin "1") (pinfunction "1_1") (pintype "passive"))
      (node (ref "C15") (pin "1") (pinfunction "1_1") (pintype "passive"))
      (node (ref "C31") (pin "1") (pinfunction "1_1") (pintype "passive"))
      (node (ref "C47") (pin "1") (pinfunction "+_1") (pintype "passive"))
      (node (ref "C48") (pin "1") (pinfunction "+_1") (pintype "passive"))
      (node (ref "C5") (pin "1") (pinfunction "1_1") (pintype "passive"))
      (node (ref "C6") (pin "1") (pinfunction "1_1") (pintype "passive"))
      (node (ref "D1") (pin "C") (pinfunction "C_C") (pintype "passive"))
      (node (ref "MIC5219-3.3YM5_1") (pin "1") (pinfunction "IN_1") (pintype "input"))
      (node (ref "MIC5219-3.3YM5_2") (pin "1") (pinfunction "IN_1") (pintype "input"))
      (node (ref "MIC5219-5.0YM1") (pin "1") (pinfunction "IN_1") (pintype "input"))
      (node (ref "MIC5219-5.0YM5") (pin "1") (pinfunction "IN_1") (pintype "input"))
      (node (ref "NCP565ST12T3G") (pin "3") (pinfunction "IN_3") (pintype "input"))
      (node (ref "R23") (pin "2") (pinfunction "2_2") (pintype "passive"))
      (node (ref "R25") (pin "2") (pinfunction "2_2") (pintype "passive"))
      (node (ref "R7") (pin "2") (pinfunction "2_2") (pintype "passive"))
      (node (ref "R8") (pin "2") (pinfunction "2_2") (pintype "passive"))
    )
    (net (code "167") (name "VCCINT") (class "Default")
      (node (ref "C16") (pin "1") (pinfunction "1_1") (pintype "passive"))
      (node (ref "C17") (pin "1") (pinfunction "1_1") (pintype "passive"))
      (node (ref "C23") (pin "1") (pinfunction "1_1") (pintype "passive"))
      (node (ref "C32") (pin "1") (pinfunction "1_1") (pintype "passive"))
      (node (ref "C40") (pin "1") (pinfunction "1_1") (pintype "passive"))
      (node (ref "C46") (pin "1") (pinfunction "+_1") (pintype "passive"))
      (node (ref "FPGA") (pin "P128") (pinfunction "VCCINT_P128") (pintype "input"))
      (node (ref "FPGA") (pin "P19") (pinfunction "VCCINT_P19") (pintype "input"))
      (node (ref "FPGA") (pin "P28") (pinfunction "VCCINT_P28") (pintype "input"))
      (node (ref "FPGA") (pin "P52") (pinfunction "VCCINT_P52") (pintype "input"))
      (node (ref "FPGA") (pin "P89") (pinfunction "VCCINT_P89") (pintype "input"))
      (node (ref "NCP565ST12T3G") (pin "2") (pinfunction "OUT_2") (pintype "passive"))
    )
    (net (code "168") (name "VCCIO") (class "Default")
      (node (ref "C12") (pin "1") (pinfunction "1_1") (pintype "passive"))
      (node (ref "C13") (pin "1") (pinfunction "1_1") (pintype "passive"))
      (node (ref "C33") (pin "1") (pinfunction "1_1") (pintype "passive"))
      (node (ref "C34") (pin "1") (pinfunction "1_1") (pintype "passive"))
      (node (ref "C35") (pin "1") (pinfunction "1_1") (pintype "passive"))
      (node (ref "C36") (pin "1") (pinfunction "1_1") (pintype "passive"))
      (node (ref "C37") (pin "1") (pinfunction "1_1") (pintype "passive"))
      (node (ref "C38") (pin "1") (pinfunction "1_1") (pintype "passive"))
      (node (ref "C39") (pin "1") (pinfunction "1_1") (pintype "passive"))
      (node (ref "FPGA") (pin "P103") (pinfunction "VCCO_1_P103") (pintype "input"))
      (node (ref "FPGA") (pin "P122") (pinfunction "VCCO_0_P122") (pintype "input"))
      (node (ref "FPGA") (pin "P125") (pinfunction "VCCO_0_P125") (pintype "input"))
      (node (ref "FPGA") (pin "P129") (pinfunction "VCCAUX_P129") (pintype "input"))
      (node (ref "FPGA") (pin "P135") (pinfunction "VCCO_0_P135") (pintype "input"))
      (node (ref "FPGA") (pin "P18") (pinfunction "VCCO_3_P18") (pintype "input"))
      (node (ref "FPGA") (pin "P20") (pinfunction "VCCAUX_P20") (pintype "input"))
      (node (ref "FPGA") (pin "P31") (pinfunction "VCCO_3_P31") (pintype "input"))
      (node (ref "FPGA") (pin "P36") (pinfunction "VCCAUX_P36") (pintype "input"))
      (node (ref "FPGA") (pin "P4") (pinfunction "VCCO_3_P4") (pintype "input"))
      (node (ref "FPGA") (pin "P42") (pinfunction "VCCO_2_P42") (pintype "input"))
      (node (ref "FPGA") (pin "P53") (pinfunction "VCCAUX_P53") (pintype "input"))
      (node (ref "FPGA") (pin "P63") (pinfunction "VCCO_2_P63") (pintype "input"))
      (node (ref "FPGA") (pin "P76") (pinfunction "VCCO_1_P76") (pintype "input"))
      (node (ref "FPGA") (pin "P86") (pinfunction "VCCO_1_P86") (pintype "input"))
      (node (ref "FPGA") (pin "P90") (pinfunction "VCCAUX_P90") (pintype "input"))
      (node (ref "FPGA_JTAG") (pin "2") (pinfunction "2_2") (pintype "passive"))
      (node (ref "MIC5219-3.3YM5_2") (pin "5") (pinfunction "OUT_5") (pintype "passive"))
      (node (ref "R27") (pin "5") (pinfunction "2_5") (pintype "passive"))
      (node (ref "R27") (pin "6") (pinfunction "2_6") (pintype "passive"))
      (node (ref "R27") (pin "7") (pinfunction "2_7") (pintype "passive"))
      (node (ref "R27") (pin "8") (pinfunction "2_8") (pintype "passive"))
      (node (ref "R28") (pin "5") (pinfunction "2_5") (pintype "passive"))
      (node (ref "R28") (pin "6") (pinfunction "2_6") (pintype "passive"))
      (node (ref "R28") (pin "7") (pinfunction "2_7") (pintype "passive"))
      (node (ref "R28") (pin "8") (pinfunction "2_8") (pintype "passive"))
      (node (ref "R34") (pin "2") (pinfunction "2_2") (pintype "passive"))
      (node (ref "R35") (pin "2") (pinfunction "2_2") (pintype "passive"))
      (node (ref "SDRAM") (pin "1") (pinfunction "VDD1_1") (pintype "bidirectional"))
      (node (ref "SDRAM") (pin "14") (pinfunction "VDD2_14") (pintype "bidirectional"))
      (node (ref "SDRAM") (pin "27") (pinfunction "VDD3_27") (pintype "bidirectional"))
      (node (ref "SDRAM") (pin "3") (pinfunction "VDDQ1_3") (pintype "bidirectional"))
      (node (ref "SDRAM") (pin "43") (pinfunction "VDDQ3_43") (pintype "bidirectional"))
      (node (ref "SDRAM") (pin "49") (pinfunction "VDDQ4_49") (pintype "bidirectional"))
      (node (ref "SDRAM") (pin "9") (pinfunction "VDDQ2_9") (pintype "bidirectional"))
      (node (ref "U$3") (pin "10") (pinfunction "VCCB_10") (pintype "bidirectional"))
    )
    (net (code "169") (name "unconnected-(ETH_PHY-25MHZ_OUT-Pad25)") (class "Default")
      (node (ref "ETH_PHY") (pin "25") (pinfunction "25MHZ_OUT_25") (pintype "bidirectional"))
    )
    (net (code "170") (name "unconnected-(ETH_PHY-COL{slash}PHYAD0-Pad42)") (class "Default")
      (node (ref "ETH_PHY") (pin "42") (pinfunction "COL/PHYAD0_42") (pintype "bidirectional"))
    )
    (net (code "171") (name "unconnected-(ETH_PHY-CRS{slash}CRS_DV{slash}LED_CFG-Pad40)") (class "Default")
      (node (ref "ETH_PHY") (pin "40") (pinfunction "CRS/CRS_DV/LED_CFG_40") (pintype "bidirectional"))
    )
    (net (code "172") (name "unconnected-(ETH_PHY-RESERVED1-Pad8)") (class "Default")
      (node (ref "ETH_PHY") (pin "8") (pinfunction "RESERVED1_8") (pintype "bidirectional"))
    )
    (net (code "173") (name "unconnected-(ETH_PHY-RESERVED2-Pad9)") (class "Default")
      (node (ref "ETH_PHY") (pin "9") (pinfunction "RESERVED2_9") (pintype "bidirectional"))
    )
    (net (code "174") (name "unconnected-(ETH_PHY-RESERVED3-Pad10)") (class "Default")
      (node (ref "ETH_PHY") (pin "10") (pinfunction "RESERVED3_10") (pintype "bidirectional"))
    )
    (net (code "175") (name "unconnected-(ETH_PHY-RESERVED4-Pad11)") (class "Default")
      (node (ref "ETH_PHY") (pin "11") (pinfunction "RESERVED4_11") (pintype "bidirectional"))
    )
    (net (code "176") (name "unconnected-(ETH_PHY-RESERVED5-Pad12)") (class "Default")
      (node (ref "ETH_PHY") (pin "12") (pinfunction "RESERVED5_12") (pintype "bidirectional"))
    )
    (net (code "177") (name "unconnected-(ETH_PHY-RESERVED6-Pad20)") (class "Default")
      (node (ref "ETH_PHY") (pin "20") (pinfunction "RESERVED6_20") (pintype "bidirectional"))
    )
    (net (code "178") (name "unconnected-(ETH_PHY-RESERVED7-Pad21)") (class "Default")
      (node (ref "ETH_PHY") (pin "21") (pinfunction "RESERVED7_21") (pintype "bidirectional"))
    )
    (net (code "179") (name "unconnected-(ETH_PHY-RXD_2{slash}PHYAD2-Pad45)") (class "Default")
      (node (ref "ETH_PHY") (pin "45") (pinfunction "RXD_2/PHYAD2_45") (pintype "bidirectional"))
    )
    (net (code "180") (name "unconnected-(ETH_PHY-RXD_3{slash}PHYAD3-Pad46)") (class "Default")
      (node (ref "ETH_PHY") (pin "46") (pinfunction "RXD_3/PHYAD3_46") (pintype "bidirectional"))
    )
    (net (code "181") (name "unconnected-(ETH_PHY-RX_CLK-Pad38)") (class "Default")
      (node (ref "ETH_PHY") (pin "38") (pinfunction "RX_CLK_38") (pintype "bidirectional"))
    )
    (net (code "182") (name "unconnected-(ETH_PHY-TXD_2-Pad5)") (class "Default")
      (node (ref "ETH_PHY") (pin "5") (pinfunction "TXD_2_5") (pintype "bidirectional"))
    )
    (net (code "183") (name "unconnected-(ETH_PHY-TX_CLK-Pad1)") (class "Default")
      (node (ref "ETH_PHY") (pin "1") (pinfunction "TX_CLK_1") (pintype "bidirectional"))
    )
    (net (code "184") (name "unconnected-(ETH_PHY-X2-Pad33)") (class "Default")
      (node (ref "ETH_PHY") (pin "33") (pinfunction "X2_33") (pintype "bidirectional"))
    )
    (net (code "185") (name "unconnected-(FPGAA-IO_L65P_SCP3_0-PadP115)") (class "Default")
      (node (ref "FPGA") (pin "P115") (pinfunction "IO_L65P_SCP3_0_P115") (pintype "bidirectional"))
    )
    (net (code "186") (name "unconnected-(FPGAB-IO_L01N_VREF_1-PadP104)") (class "Default")
      (node (ref "FPGA") (pin "P104") (pinfunction "IO_L01N_VREF_1_P104") (pintype "bidirectional"))
    )
    (net (code "187") (name "unconnected-(FPGAB-IO_L01P_1-PadP105)") (class "Default")
      (node (ref "FPGA") (pin "P105") (pinfunction "IO_L01P_1_P105") (pintype "bidirectional"))
    )
    (net (code "188") (name "unconnected-(FPGAB-IO_L32N_1-PadP101)") (class "Default")
      (node (ref "FPGA") (pin "P101") (pinfunction "IO_L32N_1_P101") (pintype "bidirectional"))
    )
    (net (code "189") (name "unconnected-(FPGAB-IO_L32P_1-PadP102)") (class "Default")
      (node (ref "FPGA") (pin "P102") (pinfunction "IO_L32P_1_P102") (pintype "bidirectional"))
    )
    (net (code "190") (name "unconnected-(FPGAB-IO_L74N_DOUT_BUSY_1-PadP74)") (class "Default")
      (node (ref "FPGA") (pin "P74") (pinfunction "IO_L74N_DOUT_BUSY_1_P74") (pintype "bidirectional"))
    )
    (net (code "191") (name "unconnected-(FPGAB-IO_L74P_AWAKE_1-PadP75)") (class "Default")
      (node (ref "FPGA") (pin "P75") (pinfunction "IO_L74P_AWAKE_1_P75") (pintype "bidirectional"))
    )
    (net (code "192") (name "unconnected-(FPGAC-CMPCS_B_2-PadP72)") (class "Default")
      (node (ref "FPGA") (pin "P72") (pinfunction "CMPCS_B_2_P72") (pintype "bidirectional"))
    )
    (net (code "193") (name "unconnected-(FPGAC-IO_L01N_M0_CMPMISO_2-PadP69)") (class "Default")
      (node (ref "FPGA") (pin "P69") (pinfunction "IO_L01N_M0_CMPMISO_2_P69") (pintype "bidirectional"))
    )
    (net (code "194") (name "unconnected-(FPGAC-IO_L64N_D9_2-PadP40)") (class "Default")
      (node (ref "FPGA") (pin "P40") (pinfunction "IO_L64N_D9_2_P40") (pintype "bidirectional"))
    )
    (net (code "195") (name "unconnected-(FPGAC-IO_L65N_CSO_B_2-PadP38)") (class "Default")
      (node (ref "FPGA") (pin "P38") (pinfunction "IO_L65N_CSO_B_2_P38") (pintype "bidirectional"))
    )
    (net (code "196") (name "unconnected-(FPGAD-IO_L01P_3-PadP35)") (class "Default")
      (node (ref "FPGA") (pin "P35") (pinfunction "IO_L01P_3_P35") (pintype "bidirectional"))
    )
    (net (code "197") (name "unconnected-(FPGA_JTAG-Pad1)") (class "Default")
      (node (ref "FPGA_JTAG") (pin "1") (pinfunction "1_1") (pintype "passive"))
    )
    (net (code "198") (name "unconnected-(FPGA_JTAG-Pad12)") (class "Default")
      (node (ref "FPGA_JTAG") (pin "12") (pinfunction "12_12") (pintype "passive"))
    )
    (net (code "199") (name "unconnected-(FPGA_JTAG-Pad14)") (class "Default")
      (node (ref "FPGA_JTAG") (pin "14") (pinfunction "14_14") (pintype "passive"))
    )
    (net (code "200") (name "unconnected-(JTAG-Pad2)") (class "Default")
      (node (ref "JTAG") (pin "2") (pinfunction "2_2") (pintype "passive"))
    )
    (net (code "201") (name "unconnected-(MCUA-BOOT0-Pad94)") (class "Default")
      (node (ref "MCU") (pin "94") (pinfunction "BOOT0_94") (pintype "bidirectional"))
    )
    (net (code "202") (name "unconnected-(MCUA-BOOT1-Pad37)") (class "Default")
      (node (ref "MCU") (pin "37") (pinfunction "BOOT1_37") (pintype "bidirectional"))
    )
    (net (code "203") (name "unconnected-(MCUA-VBAT-Pad6)") (class "Default")
      (node (ref "MCU") (pin "6") (pinfunction "VBAT_6") (pintype "bidirectional"))
    )
    (net (code "204") (name "unconnected-(MCUA-VCAP_1-Pad49)") (class "Default")
      (node (ref "MCU") (pin "49") (pinfunction "VCAP_1_49") (pintype "bidirectional"))
    )
    (net (code "205") (name "unconnected-(MCUA-VCAP_2-Pad73)") (class "Default")
      (node (ref "MCU") (pin "73") (pinfunction "VCAP_2_73") (pintype "bidirectional"))
    )
    (net (code "206") (name "unconnected-(MCUA-VDDA-Pad22)") (class "Default")
      (node (ref "MCU") (pin "22") (pinfunction "VDDA_22") (pintype "bidirectional"))
    )
    (net (code "207") (name "unconnected-(MCUA-VREFP-Pad21)") (class "Default")
      (node (ref "MCU") (pin "21") (pinfunction "VREFP_21") (pintype "bidirectional"))
    )
    (net (code "208") (name "unconnected-(MCUA-WKUP-Pad23)") (class "Default")
      (node (ref "MCU") (pin "23") (pinfunction "WKUP_23") (pintype "bidirectional"))
    )
    (net (code "209") (name "unconnected-(MCUG-SPI1_NSS-Pad29)") (class "Default")
      (node (ref "MCU") (pin "29") (pinfunction "SPI1_NSS_29") (pintype "bidirectional"))
    )
    (net (code "210") (name "unconnected-(MCUH-OSC32_IN-Pad8)") (class "Default")
      (node (ref "MCU") (pin "8") (pinfunction "OSC32_IN_8") (pintype "bidirectional"))
    )
    (net (code "211") (name "unconnected-(MCUH-OSC32_OUT-Pad9)") (class "Default")
      (node (ref "MCU") (pin "9") (pinfunction "OSC32_OUT_9") (pintype "bidirectional"))
    )
    (net (code "212") (name "unconnected-(MCUI-PB6-Pad92)") (class "Default")
      (node (ref "MCU") (pin "92") (pinfunction "PB6_92") (pintype "bidirectional"))
    )
    (net (code "213") (name "unconnected-(MCUI-PB8-Pad95)") (class "Default")
      (node (ref "MCU") (pin "95") (pinfunction "PB8_95") (pintype "bidirectional"))
    )
    (net (code "214") (name "unconnected-(MCUI-PB9-Pad96)") (class "Default")
      (node (ref "MCU") (pin "96") (pinfunction "PB9_96") (pintype "bidirectional"))
    )
    (net (code "215") (name "unconnected-(MCUI-PC0-Pad15)") (class "Default")
      (node (ref "MCU") (pin "15") (pinfunction "PC0_15") (pintype "bidirectional"))
    )
    (net (code "216") (name "unconnected-(MCUI-PC2-Pad17)") (class "Default")
      (node (ref "MCU") (pin "17") (pinfunction "PC2_17") (pintype "bidirectional"))
    )
    (net (code "217") (name "unconnected-(MCUI-PC3-Pad18)") (class "Default")
      (node (ref "MCU") (pin "18") (pinfunction "PC3_18") (pintype "bidirectional"))
    )
    (net (code "218") (name "unconnected-(MCUI-PC13-Pad7)") (class "Default")
      (node (ref "MCU") (pin "7") (pinfunction "PC13_7") (pintype "bidirectional"))
    )
    (net (code "219") (name "unconnected-(MICROSD-SHIELD-PadCD2)") (class "Default")
      (node (ref "MICROSD") (pin "CD2") (pinfunction "SHIELD_CD2") (pintype "bidirectional"))
    )
    (net (code "220") (name "unconnected-(SDRAM-NC-Pad40)") (class "Default")
      (node (ref "SDRAM") (pin "40") (pinfunction "NC_40") (pintype "bidirectional"))
    )
    (net (code "221") (name "unconnected-(U$3-EN-Pad6)") (class "Default")
      (node (ref "U$3") (pin "6") (pinfunction "EN_6") (pintype "bidirectional"))
    )
  )
)
